# io-board-b-9.net
KiCad netlist of a schematic drawn in EAGLE
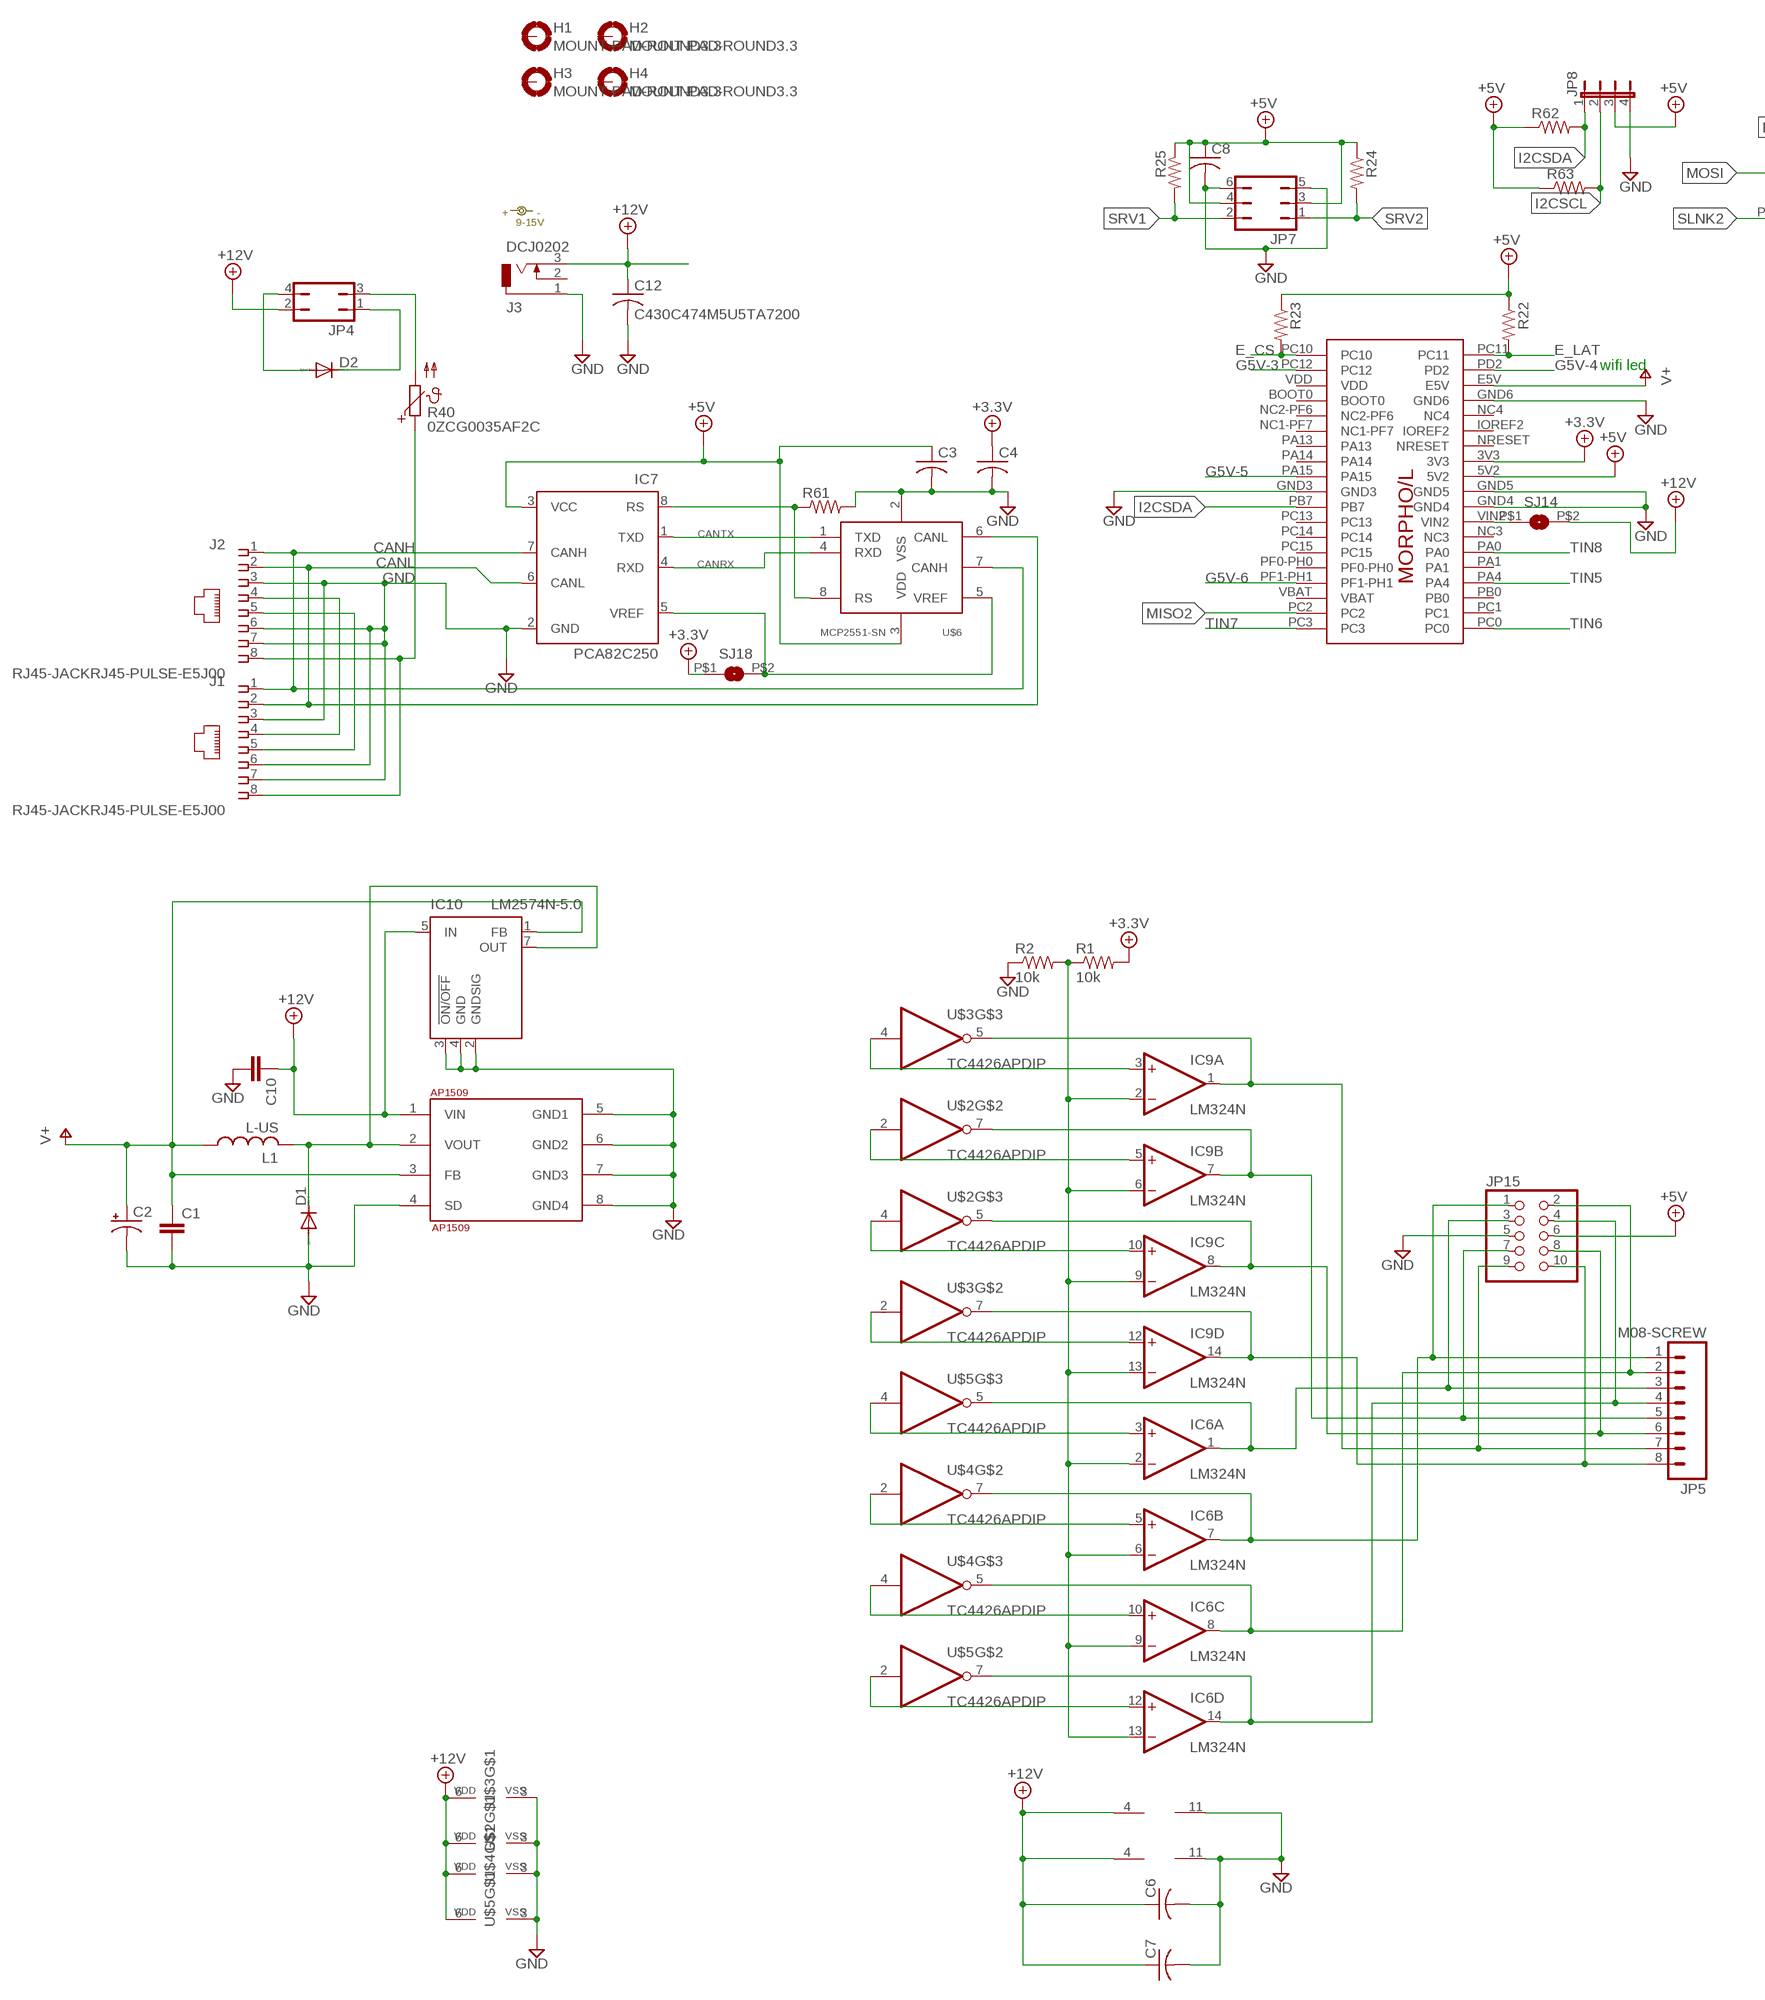
[diagram p0: schematic, sheet 1, part 1 of 2]
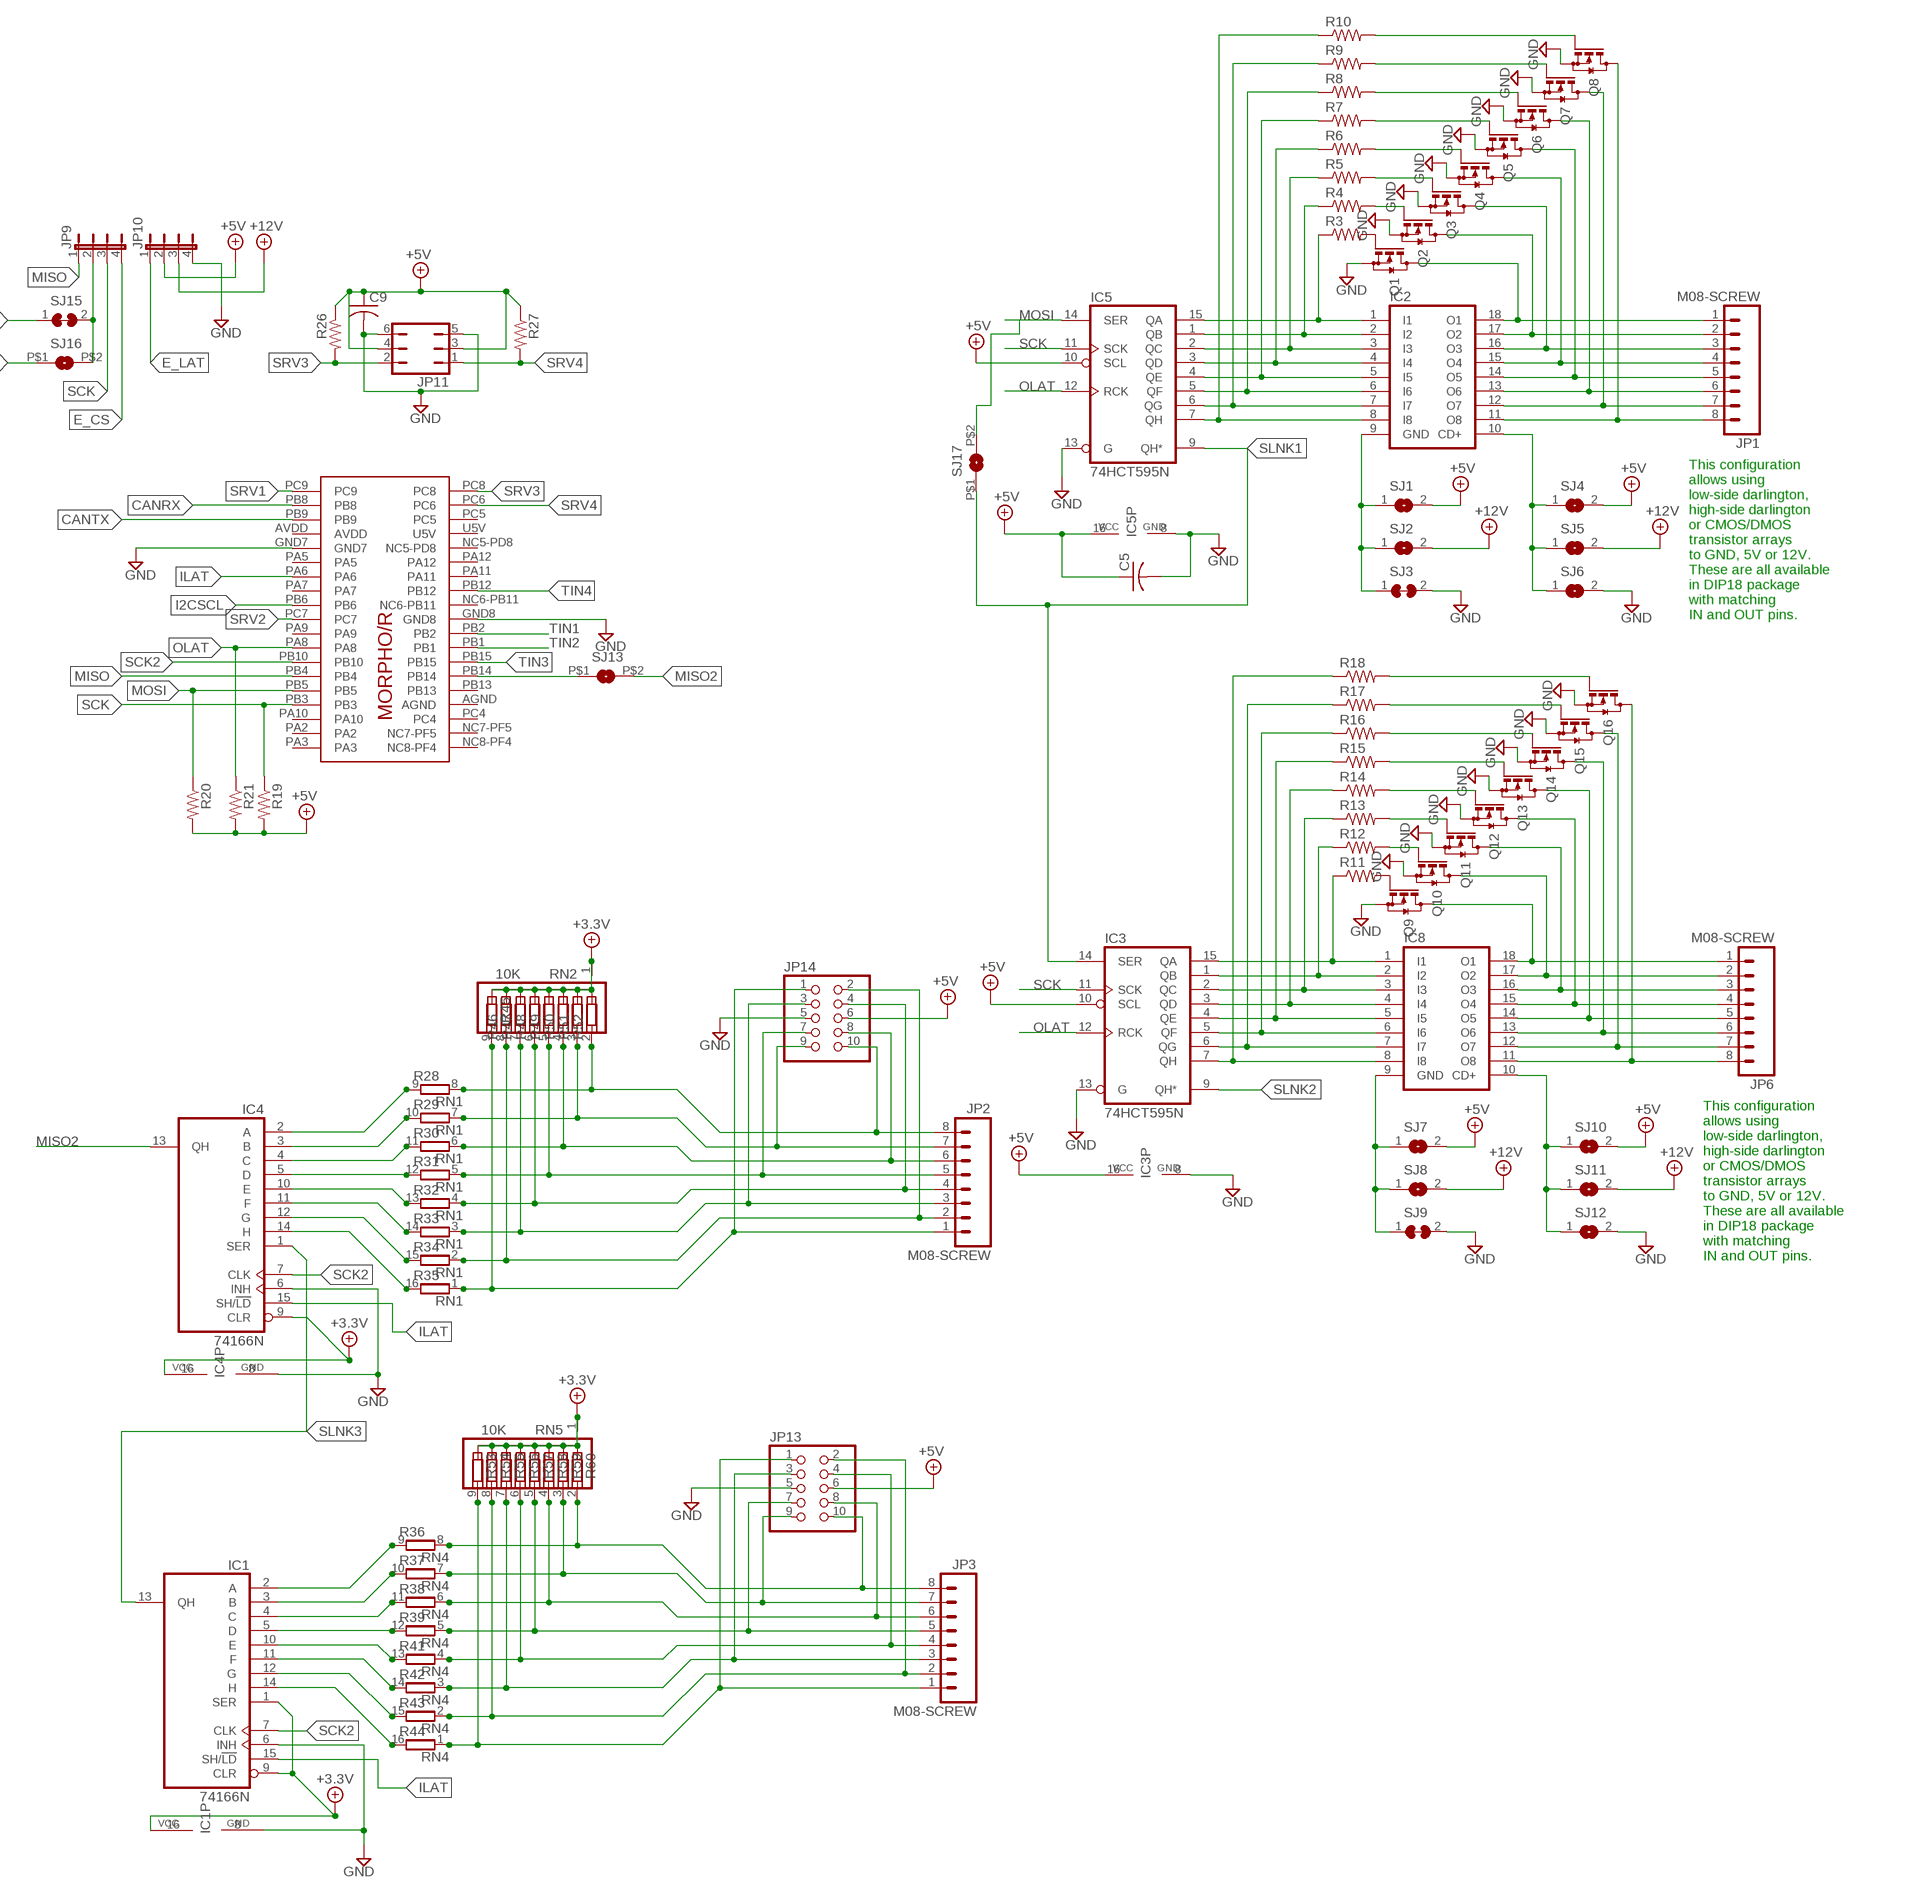
[diagram p1: schematic, sheet 1, part 2 of 2]

(export (version "E")
  (design (tool "Eeschema 10.0.6"))
  (components
    (comp (ref "+12V")
      (value "9-15V")
      (footprint "eagle-import:POWER_USAGE")
      (libsource (lib "eagle-import") (part "DOC-POWER_LABEL"))
    )
    (comp (ref "AP1509")
      (value "AP1509")
      (footprint "eagle-import:SO-08")
      (libsource (lib "eagle-import") (part "AP1509"))
    )
    (comp (ref "C1")
      (value "C-EUC1206")
      (footprint "eagle-import:C1206")
      (libsource (lib "eagle-import") (part "C-EUC1206"))
    )
    (comp (ref "C2")
      (value "CPOL-USE2.5-5")
      (footprint "eagle-import:E2,5-5")
      (libsource (lib "eagle-import") (part "CPOL-USE2.5-5"))
    )
    (comp (ref "C3")
      (value "C-USC0805")
      (footprint "eagle-import:C0805")
      (libsource (lib "eagle-import") (part "C-USC0805"))
    )
    (comp (ref "C4")
      (value "C-USC0805")
      (footprint "eagle-import:C0805")
      (libsource (lib "eagle-import") (part "C-USC0805"))
    )
    (comp (ref "C5")
      (value "C-USC0805")
      (footprint "eagle-import:C0805")
      (libsource (lib "eagle-import") (part "C-USC0805"))
    )
    (comp (ref "C6")
      (value "C-USC1206")
      (footprint "eagle-import:C1206")
      (libsource (lib "eagle-import") (part "C-USC1206"))
    )
    (comp (ref "C7")
      (value "C-USC1206")
      (footprint "eagle-import:C1206")
      (libsource (lib "eagle-import") (part "C-USC1206"))
    )
    (comp (ref "C8")
      (value "C-USC1206")
      (footprint "eagle-import:C1206")
      (libsource (lib "eagle-import") (part "C-USC1206"))
    )
    (comp (ref "C9")
      (value "C-USC1206")
      (footprint "eagle-import:C1206")
      (libsource (lib "eagle-import") (part "C-USC1206"))
    )
    (comp (ref "C10")
      (value "C-EUC1206")
      (footprint "eagle-import:C1206")
      (libsource (lib "eagle-import") (part "C-EUC1206"))
    )
    (comp (ref "C12")
      (value "C430C474M5U5TA7200")
      (footprint "eagle-import:C075-032X103")
      (libsource (lib "eagle-import") (part "C-US075-032X103"))
    )
    (comp (ref "D1")
      (value "DIODE-DO41-7.6")
      (footprint "eagle-import:DO41-7.6")
      (libsource (lib "eagle-import") (part "DIODE-DO41-7.6"))
    )
    (comp (ref "D2")
      (value "DIODE-DO41-7.6")
      (footprint "eagle-import:DO41-7.6")
      (libsource (lib "eagle-import") (part "DIODE-DO41-7.6"))
    )
    (comp (ref "H1")
      (value "MOUNT-PAD-ROUND3.3")
      (footprint "eagle-import:3,3-PAD")
      (libsource (lib "eagle-import") (part "MOUNT-PAD-ROUND3.3"))
    )
    (comp (ref "H2")
      (value "MOUNT-PAD-ROUND3.3")
      (footprint "eagle-import:3,3-PAD")
      (libsource (lib "eagle-import") (part "MOUNT-PAD-ROUND3.3"))
    )
    (comp (ref "H3")
      (value "MOUNT-PAD-ROUND3.3")
      (footprint "eagle-import:3,3-PAD")
      (libsource (lib "eagle-import") (part "MOUNT-PAD-ROUND3.3"))
    )
    (comp (ref "H4")
      (value "MOUNT-PAD-ROUND3.3")
      (footprint "eagle-import:3,3-PAD")
      (libsource (lib "eagle-import") (part "MOUNT-PAD-ROUND3.3"))
    )
    (comp (ref "IC1")
      (value "74166N")
      (footprint "eagle-import:DIL16")
      (libsource (lib "eagle-import") (part "74166N"))
    )
    (comp (ref "IC2")
      (value "ULN2803A")
      (footprint "eagle-import:DIL18-THIN")
      (libsource (lib "eagle-import") (part "ULN2803A"))
    )
    (comp (ref "IC3")
      (value "74HCT595N")
      (footprint "eagle-import:DIL16")
      (libsource (lib "eagle-import") (part "74595NHCT"))
    )
    (comp (ref "IC4")
      (value "74166N")
      (footprint "eagle-import:DIL16")
      (libsource (lib "eagle-import") (part "74166N"))
    )
    (comp (ref "IC5")
      (value "74HCT595N")
      (footprint "eagle-import:DIL16")
      (libsource (lib "eagle-import") (part "74595NHCT"))
    )
    (comp (ref "IC6")
      (value "LM324N")
      (footprint "eagle-import:DIL14")
      (libsource (lib "eagle-import") (part "LM324N"))
    )
    (comp (ref "IC7")
      (value "PCA82C250")
      (footprint "eagle-import:DIL08")
      (libsource (lib "eagle-import") (part "PCA82C250"))
    )
    (comp (ref "IC8")
      (value "ULN2803A")
      (footprint "eagle-import:DIL18-THIN")
      (libsource (lib "eagle-import") (part "ULN2803A"))
    )
    (comp (ref "IC9")
      (value "LM324N")
      (footprint "eagle-import:DIL14")
      (libsource (lib "eagle-import") (part "LM324N"))
    )
    (comp (ref "IC10")
      (value "LM2574N-5.0")
      (footprint "eagle-import:DIL08")
      (libsource (lib "eagle-import") (part "LM2574?-N5.0"))
    )
    (comp (ref "J1")
      (value "RJ45-JACKRJ45-PULSE-E5J00")
      (footprint "eagle-import:RJ45-PULSE-E5J88")
      (libsource (lib "eagle-import") (part "RJ45-JACKRJ45-PULSE-E5J00"))
    )
    (comp (ref "J2")
      (value "RJ45-JACKRJ45-PULSE-E5J00")
      (footprint "eagle-import:RJ45-PULSE-E5J88")
      (libsource (lib "eagle-import") (part "RJ45-JACKRJ45-PULSE-E5J00"))
    )
    (comp (ref "J3")
      (value "DCJ0202")
      (footprint "eagle-import:DCJ0202")
      (libsource (lib "eagle-import") (part "DCJ0202"))
    )
    (comp (ref "JP1")
      (value "M08-SCREW")
      (footprint "eagle-import:1X08_TERMINAL")
      (libsource (lib "eagle-import") (part "M08-SCREW"))
    )
    (comp (ref "JP2")
      (value "M08-SCREW")
      (footprint "eagle-import:1X08_TERMINAL")
      (libsource (lib "eagle-import") (part "M08-SCREW"))
    )
    (comp (ref "JP3")
      (value "M08-SCREW")
      (footprint "eagle-import:1X08_TERMINAL")
      (libsource (lib "eagle-import") (part "M08-SCREW"))
    )
    (comp (ref "JP4")
      (value "JP2Q")
      (footprint "eagle-import:JP2Q")
      (libsource (lib "eagle-import") (part "JP2Q"))
    )
    (comp (ref "JP5")
      (value "M08-SCREW")
      (footprint "eagle-import:1X08_TERMINAL")
      (libsource (lib "eagle-import") (part "M08-SCREW"))
    )
    (comp (ref "JP6")
      (value "M08-SCREW")
      (footprint "eagle-import:1X08_TERMINAL")
      (libsource (lib "eagle-import") (part "M08-SCREW"))
    )
    (comp (ref "JP7")
      (value "JP3Q")
      (footprint "eagle-import:JP3Q")
      (libsource (lib "eagle-import") (part "JP3Q"))
    )
    (comp (ref "JP8")
      (value "JP4-FLAT")
      (footprint "eagle-import:JP4F")
      (libsource (lib "eagle-import") (part "JP4-FLAT"))
    )
    (comp (ref "JP9")
      (value "JP4-FLAT")
      (footprint "eagle-import:JP4F")
      (libsource (lib "eagle-import") (part "JP4-FLAT"))
    )
    (comp (ref "JP10")
      (value "JP4-FLAT")
      (footprint "eagle-import:JP4F")
      (libsource (lib "eagle-import") (part "JP4-FLAT"))
    )
    (comp (ref "JP11")
      (value "JP3Q")
      (footprint "eagle-import:JP3Q")
      (libsource (lib "eagle-import") (part "JP3Q"))
    )
    (comp (ref "JP13")
      (value "PINHD-2X5CN")
      (footprint "eagle-import:CON10M")
      (libsource (lib "eagle-import") (part "PINHD-2X5CN"))
    )
    (comp (ref "JP14")
      (value "PINHD-2X5CN")
      (footprint "eagle-import:CON10M")
      (libsource (lib "eagle-import") (part "PINHD-2X5CN"))
    )
    (comp (ref "JP15")
      (value "PINHD-2X5CN")
      (footprint "eagle-import:CON10M")
      (libsource (lib "eagle-import") (part "PINHD-2X5CN"))
    )
    (comp (ref "L1")
      (value "L-US")
      (footprint "eagle-import:L5-8,5")
      (libsource (lib "eagle-import") (part "L-US"))
    )
    (comp (ref "Q1")
      (value "BSS123")
      (footprint "eagle-import:SOT23")
      (libsource (lib "eagle-import") (part "BSS123"))
    )
    (comp (ref "Q2")
      (value "BSS123")
      (footprint "eagle-import:SOT23")
      (libsource (lib "eagle-import") (part "BSS123"))
    )
    (comp (ref "Q3")
      (value "BSS123")
      (footprint "eagle-import:SOT23")
      (libsource (lib "eagle-import") (part "BSS123"))
    )
    (comp (ref "Q4")
      (value "BSS123")
      (footprint "eagle-import:SOT23")
      (libsource (lib "eagle-import") (part "BSS123"))
    )
    (comp (ref "Q5")
      (value "BSS123")
      (footprint "eagle-import:SOT23")
      (libsource (lib "eagle-import") (part "BSS123"))
    )
    (comp (ref "Q6")
      (value "BSS123")
      (footprint "eagle-import:SOT23")
      (libsource (lib "eagle-import") (part "BSS123"))
    )
    (comp (ref "Q7")
      (value "BSS123")
      (footprint "eagle-import:SOT23")
      (libsource (lib "eagle-import") (part "BSS123"))
    )
    (comp (ref "Q8")
      (value "BSS123")
      (footprint "eagle-import:SOT23")
      (libsource (lib "eagle-import") (part "BSS123"))
    )
    (comp (ref "Q9")
      (value "BSS123")
      (footprint "eagle-import:SOT23")
      (libsource (lib "eagle-import") (part "BSS123"))
    )
    (comp (ref "Q10")
      (value "BSS123")
      (footprint "eagle-import:SOT23")
      (libsource (lib "eagle-import") (part "BSS123"))
    )
    (comp (ref "Q11")
      (value "BSS123")
      (footprint "eagle-import:SOT23")
      (libsource (lib "eagle-import") (part "BSS123"))
    )
    (comp (ref "Q12")
      (value "BSS123")
      (footprint "eagle-import:SOT23")
      (libsource (lib "eagle-import") (part "BSS123"))
    )
    (comp (ref "Q13")
      (value "BSS123")
      (footprint "eagle-import:SOT23")
      (libsource (lib "eagle-import") (part "BSS123"))
    )
    (comp (ref "Q14")
      (value "BSS123")
      (footprint "eagle-import:SOT23")
      (libsource (lib "eagle-import") (part "BSS123"))
    )
    (comp (ref "Q15")
      (value "BSS123")
      (footprint "eagle-import:SOT23")
      (libsource (lib "eagle-import") (part "BSS123"))
    )
    (comp (ref "Q16")
      (value "BSS123")
      (footprint "eagle-import:SOT23")
      (libsource (lib "eagle-import") (part "BSS123"))
    )
    (comp (ref "R1")
      (value "10k")
      (footprint "eagle-import:R0805")
      (libsource (lib "eagle-import") (part "R-US_R0805"))
    )
    (comp (ref "R2")
      (value "10k")
      (footprint "eagle-import:R0805")
      (libsource (lib "eagle-import") (part "R-US_R0805"))
    )
    (comp (ref "R3")
      (value "R-US_R0603")
      (footprint "eagle-import:R0603")
      (libsource (lib "eagle-import") (part "R-US_R0603"))
    )
    (comp (ref "R4")
      (value "R-US_R0603")
      (footprint "eagle-import:R0603")
      (libsource (lib "eagle-import") (part "R-US_R0603"))
    )
    (comp (ref "R5")
      (value "R-US_R0603")
      (footprint "eagle-import:R0603")
      (libsource (lib "eagle-import") (part "R-US_R0603"))
    )
    (comp (ref "R6")
      (value "R-US_R0603")
      (footprint "eagle-import:R0603")
      (libsource (lib "eagle-import") (part "R-US_R0603"))
    )
    (comp (ref "R7")
      (value "R-US_R0603")
      (footprint "eagle-import:R0603")
      (libsource (lib "eagle-import") (part "R-US_R0603"))
    )
    (comp (ref "R8")
      (value "R-US_R0603")
      (footprint "eagle-import:R0603")
      (libsource (lib "eagle-import") (part "R-US_R0603"))
    )
    (comp (ref "R9")
      (value "R-US_R0603")
      (footprint "eagle-import:R0603")
      (libsource (lib "eagle-import") (part "R-US_R0603"))
    )
    (comp (ref "R10")
      (value "R-US_R0603")
      (footprint "eagle-import:R0603")
      (libsource (lib "eagle-import") (part "R-US_R0603"))
    )
    (comp (ref "R11")
      (value "R-US_R0603")
      (footprint "eagle-import:R0603")
      (libsource (lib "eagle-import") (part "R-US_R0603"))
    )
    (comp (ref "R12")
      (value "R-US_R0603")
      (footprint "eagle-import:R0603")
      (libsource (lib "eagle-import") (part "R-US_R0603"))
    )
    (comp (ref "R13")
      (value "R-US_R0603")
      (footprint "eagle-import:R0603")
      (libsource (lib "eagle-import") (part "R-US_R0603"))
    )
    (comp (ref "R14")
      (value "R-US_R0603")
      (footprint "eagle-import:R0603")
      (libsource (lib "eagle-import") (part "R-US_R0603"))
    )
    (comp (ref "R15")
      (value "R-US_R0603")
      (footprint "eagle-import:R0603")
      (libsource (lib "eagle-import") (part "R-US_R0603"))
    )
    (comp (ref "R16")
      (value "R-US_R0603")
      (footprint "eagle-import:R0603")
      (libsource (lib "eagle-import") (part "R-US_R0603"))
    )
    (comp (ref "R17")
      (value "R-US_R0603")
      (footprint "eagle-import:R0603")
      (libsource (lib "eagle-import") (part "R-US_R0603"))
    )
    (comp (ref "R18")
      (value "R-US_R0603")
      (footprint "eagle-import:R0603")
      (libsource (lib "eagle-import") (part "R-US_R0603"))
    )
    (comp (ref "R19")
      (value "R-US_R0805")
      (footprint "eagle-import:R0805")
      (libsource (lib "eagle-import") (part "rcl_334_R-US_R0805"))
    )
    (comp (ref "R20")
      (value "R-US_R0805")
      (footprint "eagle-import:R0805")
      (libsource (lib "eagle-import") (part "rcl_334_R-US_R0805"))
    )
    (comp (ref "R21")
      (value "R-US_R0805")
      (footprint "eagle-import:R0805")
      (libsource (lib "eagle-import") (part "rcl_334_R-US_R0805"))
    )
    (comp (ref "R22")
      (value "R-US_R0805")
      (footprint "eagle-import:R0805")
      (libsource (lib "eagle-import") (part "rcl_334_R-US_R0805"))
    )
    (comp (ref "R23")
      (value "R-US_R0805")
      (footprint "eagle-import:R0805")
      (libsource (lib "eagle-import") (part "rcl_334_R-US_R0805"))
    )
    (comp (ref "R24")
      (value "R-US_R0805")
      (footprint "eagle-import:R0805")
      (libsource (lib "eagle-import") (part "rcl_334_R-US_R0805"))
    )
    (comp (ref "R25")
      (value "R-US_R0805")
      (footprint "eagle-import:R0805")
      (libsource (lib "eagle-import") (part "rcl_334_R-US_R0805"))
    )
    (comp (ref "R26")
      (value "R-US_R0805")
      (footprint "eagle-import:R0805")
      (libsource (lib "eagle-import") (part "rcl_334_R-US_R0805"))
    )
    (comp (ref "R27")
      (value "R-US_R0805")
      (footprint "eagle-import:R0805")
      (libsource (lib "eagle-import") (part "rcl_334_R-US_R0805"))
    )
    (comp (ref "R28")
      (value "R-EU_R0603")
      (footprint "eagle-import:R0603")
      (libsource (lib "eagle-import") (part "R-EU_R0603"))
    )
    (comp (ref "R29")
      (value "R-EU_R0603")
      (footprint "eagle-import:R0603")
      (libsource (lib "eagle-import") (part "R-EU_R0603"))
    )
    (comp (ref "R30")
      (value "R-EU_R0603")
      (footprint "eagle-import:R0603")
      (libsource (lib "eagle-import") (part "R-EU_R0603"))
    )
    (comp (ref "R31")
      (value "R-EU_R0603")
      (footprint "eagle-import:R0603")
      (libsource (lib "eagle-import") (part "R-EU_R0603"))
    )
    (comp (ref "R32")
      (value "R-EU_R0603")
      (footprint "eagle-import:R0603")
      (libsource (lib "eagle-import") (part "R-EU_R0603"))
    )
    (comp (ref "R33")
      (value "R-EU_R0603")
      (footprint "eagle-import:R0603")
      (libsource (lib "eagle-import") (part "R-EU_R0603"))
    )
    (comp (ref "R34")
      (value "R-EU_R0603")
      (footprint "eagle-import:R0603")
      (libsource (lib "eagle-import") (part "R-EU_R0603"))
    )
    (comp (ref "R35")
      (value "R-EU_R0603")
      (footprint "eagle-import:R0603")
      (libsource (lib "eagle-import") (part "R-EU_R0603"))
    )
    (comp (ref "R36")
      (value "R-EU_R0603")
      (footprint "eagle-import:R0603")
      (libsource (lib "eagle-import") (part "R-EU_R0603"))
    )
    (comp (ref "R37")
      (value "R-EU_R0603")
      (footprint "eagle-import:R0603")
      (libsource (lib "eagle-import") (part "R-EU_R0603"))
    )
    (comp (ref "R38")
      (value "R-EU_R0603")
      (footprint "eagle-import:R0603")
      (libsource (lib "eagle-import") (part "R-EU_R0603"))
    )
    (comp (ref "R39")
      (value "R-EU_R0603")
      (footprint "eagle-import:R0603")
      (libsource (lib "eagle-import") (part "R-EU_R0603"))
    )
    (comp (ref "R40")
      (value "0ZCG0035AF2C")
      (footprint "eagle-import:PTC1812")
      (libsource (lib "eagle-import") (part "PTC_1812"))
    )
    (comp (ref "R41")
      (value "R-EU_R0603")
      (footprint "eagle-import:R0603")
      (libsource (lib "eagle-import") (part "R-EU_R0603"))
    )
    (comp (ref "R42")
      (value "R-EU_R0603")
      (footprint "eagle-import:R0603")
      (libsource (lib "eagle-import") (part "R-EU_R0603"))
    )
    (comp (ref "R43")
      (value "R-EU_R0603")
      (footprint "eagle-import:R0603")
      (libsource (lib "eagle-import") (part "R-EU_R0603"))
    )
    (comp (ref "R44")
      (value "R-EU_R0603")
      (footprint "eagle-import:R0603")
      (libsource (lib "eagle-import") (part "R-EU_R0603"))
    )
    (comp (ref "R45")
      (value "R-EU_R0603")
      (footprint "eagle-import:R0603")
      (libsource (lib "eagle-import") (part "R-EU_R0603"))
    )
    (comp (ref "R46")
      (value "R-EU_R0603")
      (footprint "eagle-import:R0603")
      (libsource (lib "eagle-import") (part "R-EU_R0603"))
    )
    (comp (ref "R47")
      (value "R-EU_R0603")
      (footprint "eagle-import:R0603")
      (libsource (lib "eagle-import") (part "R-EU_R0603"))
    )
    (comp (ref "R48")
      (value "R-EU_R0603")
      (footprint "eagle-import:R0603")
      (libsource (lib "eagle-import") (part "R-EU_R0603"))
    )
    (comp (ref "R49")
      (value "R-EU_R0603")
      (footprint "eagle-import:R0603")
      (libsource (lib "eagle-import") (part "R-EU_R0603"))
    )
    (comp (ref "R50")
      (value "R-EU_R0603")
      (footprint "eagle-import:R0603")
      (libsource (lib "eagle-import") (part "R-EU_R0603"))
    )
    (comp (ref "R51")
      (value "R-EU_R0603")
      (footprint "eagle-import:R0603")
      (libsource (lib "eagle-import") (part "R-EU_R0603"))
    )
    (comp (ref "R52")
      (value "R-EU_R0603")
      (footprint "eagle-import:R0603")
      (libsource (lib "eagle-import") (part "R-EU_R0603"))
    )
    (comp (ref "R53")
      (value "R-EU_R0603")
      (footprint "eagle-import:R0603")
      (libsource (lib "eagle-import") (part "R-EU_R0603"))
    )
    (comp (ref "R54")
      (value "R-EU_R0603")
      (footprint "eagle-import:R0603")
      (libsource (lib "eagle-import") (part "R-EU_R0603"))
    )
    (comp (ref "R55")
      (value "R-EU_R0603")
      (footprint "eagle-import:R0603")
      (libsource (lib "eagle-import") (part "R-EU_R0603"))
    )
    (comp (ref "R56")
      (value "R-EU_R0603")
      (footprint "eagle-import:R0603")
      (libsource (lib "eagle-import") (part "R-EU_R0603"))
    )
    (comp (ref "R57")
      (value "R-EU_R0603")
      (footprint "eagle-import:R0603")
      (libsource (lib "eagle-import") (part "R-EU_R0603"))
    )
    (comp (ref "R58")
      (value "R-EU_R0603")
      (footprint "eagle-import:R0603")
      (libsource (lib "eagle-import") (part "R-EU_R0603"))
    )
    (comp (ref "R59")
      (value "R-EU_R0603")
      (footprint "eagle-import:R0603")
      (libsource (lib "eagle-import") (part "R-EU_R0603"))
    )
    (comp (ref "R60")
      (value "R-EU_R0603")
      (footprint "eagle-import:R0603")
      (libsource (lib "eagle-import") (part "R-EU_R0603"))
    )
    (comp (ref "R61")
      (value "R-US_R0805")
      (footprint "eagle-import:R0805")
      (libsource (lib "eagle-import") (part "rcl_334_R-US_R0805"))
    )
    (comp (ref "R62")
      (value "R-US_R0805")
      (footprint "eagle-import:R0805")
      (libsource (lib "eagle-import") (part "rcl_334_R-US_R0805"))
    )
    (comp (ref "R63")
      (value "R-US_R0805")
      (footprint "eagle-import:R0805")
      (libsource (lib "eagle-import") (part "rcl_334_R-US_R0805"))
    )
    (comp (ref "RN1")
      (value "8R-P")
      (footprint "eagle-import:DIL16")
      (libsource (lib "eagle-import") (part "8R-P"))
    )
    (comp (ref "RN2")
      (value "10K")
      (footprint "eagle-import:SIL9")
      (libsource (lib "eagle-import") (part "G08R"))
    )
    (comp (ref "RN4")
      (value "8R-P")
      (footprint "eagle-import:DIL16")
      (libsource (lib "eagle-import") (part "8R-P"))
    )
    (comp (ref "RN5")
      (value "10K")
      (footprint "eagle-import:SIL9")
      (libsource (lib "eagle-import") (part "G08R"))
    )
    (comp (ref "SJ1")
      (value "SJ")
      (footprint "eagle-import:SJ-RND")
      (libsource (lib "eagle-import") (part "SJ"))
    )
    (comp (ref "SJ2")
      (value "SJ")
      (footprint "eagle-import:SJ-RND")
      (libsource (lib "eagle-import") (part "SJ"))
    )
    (comp (ref "SJ3")
      (value "SJ-C")
      (footprint "eagle-import:SJW-C")
      (libsource (lib "eagle-import") (part "SJ-C"))
    )
    (comp (ref "SJ4")
      (value "SJ")
      (footprint "eagle-import:SJ-RND")
      (libsource (lib "eagle-import") (part "SJ"))
    )
    (comp (ref "SJ5")
      (value "SJ")
      (footprint "eagle-import:SJ-RND")
      (libsource (lib "eagle-import") (part "SJ"))
    )
    (comp (ref "SJ6")
      (value "SJ")
      (footprint "eagle-import:SJ-RND")
      (libsource (lib "eagle-import") (part "SJ"))
    )
    (comp (ref "SJ7")
      (value "SJ")
      (footprint "eagle-import:SJ-RND")
      (libsource (lib "eagle-import") (part "SJ"))
    )
    (comp (ref "SJ8")
      (value "SJ")
      (footprint "eagle-import:SJ-RND")
      (libsource (lib "eagle-import") (part "SJ"))
    )
    (comp (ref "SJ9")
      (value "SJ-C")
      (footprint "eagle-import:SJW-C")
      (libsource (lib "eagle-import") (part "SJ-C"))
    )
    (comp (ref "SJ10")
      (value "SJ")
      (footprint "eagle-import:SJ-RND")
      (libsource (lib "eagle-import") (part "SJ"))
    )
    (comp (ref "SJ11")
      (value "SJ")
      (footprint "eagle-import:SJ-RND")
      (libsource (lib "eagle-import") (part "SJ"))
    )
    (comp (ref "SJ12")
      (value "SJ")
      (footprint "eagle-import:SJ-RND")
      (libsource (lib "eagle-import") (part "SJ"))
    )
    (comp (ref "SJ13")
      (value "SJRND2")
      (footprint "eagle-import:SJ_RND2")
      (libsource (lib "eagle-import") (part "SJRND2"))
    )
    (comp (ref "SJ14")
      (value "SJRND2")
      (footprint "eagle-import:SJ_RND2")
      (libsource (lib "eagle-import") (part "SJRND2"))
    )
    (comp (ref "SJ15")
      (value "SJ-C")
      (footprint "eagle-import:SJW-C")
      (libsource (lib "eagle-import") (part "SJ-C"))
    )
    (comp (ref "SJ16")
      (value "SJRND2")
      (footprint "eagle-import:SJ_RND2")
      (libsource (lib "eagle-import") (part "SJRND2"))
    )
    (comp (ref "SJ17")
      (value "SJRND2")
      (footprint "eagle-import:SJ_RND2")
      (libsource (lib "eagle-import") (part "SJRND2"))
    )
    (comp (ref "SJ18")
      (value "SJRND2")
      (footprint "eagle-import:SJ_RND2")
      (libsource (lib "eagle-import") (part "SJRND2"))
    )
    (comp (ref "U$1")
      (value "NUCLEO_64_GENERIC")
      (footprint "eagle-import:NUCLEO_BRD_BASE64")
      (libsource (lib "eagle-import") (part "NUCLEO_64_GENERIC"))
    )
    (comp (ref "U$2")
      (value "TC4426APDIP")
      (footprint "eagle-import:DIL08-LONG")
      (libsource (lib "eagle-import") (part "TC4426APDIP"))
    )
    (comp (ref "U$3")
      (value "TC4426APDIP")
      (footprint "eagle-import:DIL08-LONG")
      (libsource (lib "eagle-import") (part "TC4426APDIP"))
    )
    (comp (ref "U$4")
      (value "TC4426APDIP")
      (footprint "eagle-import:DIL08-LONG")
      (libsource (lib "eagle-import") (part "TC4426APDIP"))
    )
    (comp (ref "U$5")
      (value "TC4426APDIP")
      (footprint "eagle-import:DIL08-LONG")
      (libsource (lib "eagle-import") (part "TC4426APDIP"))
    )
    (comp (ref "U$6")
      (value "MCP2551-SN")
      (footprint "eagle-import:SO-08")
      (libsource (lib "eagle-import") (part "MCP2551-SN"))
    )
  )
  (nets
    (net (code "1") (name "+3.3V") (class "Default")
      (node (ref "C4") (pin "1") (pinfunction "1_1") (pintype "passive"))
      (node (ref "IC1") (pin "1") (pinfunction "SER_1") (pintype "input"))
      (node (ref "IC1") (pin "16") (pinfunction "VCC_16") (pintype "power_in"))
      (node (ref "IC1") (pin "9") (pinfunction "CLR_9") (pintype "input"))
      (node (ref "IC4") (pin "16") (pinfunction "VCC_16") (pintype "power_in"))
      (node (ref "IC4") (pin "9") (pinfunction "CLR_9") (pintype "input"))
      (node (ref "R1") (pin "2") (pinfunction "2_2") (pintype "passive"))
      (node (ref "R45") (pin "1") (pinfunction "1_1") (pintype "passive"))
      (node (ref "R46") (pin "2") (pinfunction "2_2") (pintype "passive"))
      (node (ref "R47") (pin "2") (pinfunction "2_2") (pintype "passive"))
      (node (ref "R48") (pin "2") (pinfunction "2_2") (pintype "passive"))
      (node (ref "R49") (pin "2") (pinfunction "2_2") (pintype "passive"))
      (node (ref "R50") (pin "2") (pinfunction "2_2") (pintype "passive"))
      (node (ref "R51") (pin "2") (pinfunction "2_2") (pintype "passive"))
      (node (ref "R52") (pin "2") (pinfunction "2_2") (pintype "passive"))
      (node (ref "R53") (pin "1") (pinfunction "1_1") (pintype "passive"))
      (node (ref "R54") (pin "1") (pinfunction "1_1") (pintype "passive"))
      (node (ref "R55") (pin "1") (pinfunction "1_1") (pintype "passive"))
      (node (ref "R56") (pin "1") (pinfunction "1_1") (pintype "passive"))
      (node (ref "R57") (pin "1") (pinfunction "1_1") (pintype "passive"))
      (node (ref "R58") (pin "1") (pinfunction "1_1") (pintype "passive"))
      (node (ref "R59") (pin "1") (pinfunction "1_1") (pintype "passive"))
      (node (ref "R60") (pin "1") (pinfunction "1_1") (pintype "passive"))
      (node (ref "RN2") (pin "1") (pinfunction "1_1") (pintype "passive"))
      (node (ref "RN5") (pin "1") (pinfunction "1_1") (pintype "passive"))
      (node (ref "SJ18") (pin "P$1") (pinfunction "1_P$1") (pintype "passive"))
      (node (ref "U$1") (pin "3V3") (pinfunction "3V3_3V3") (pintype "power_in"))
    )
    (net (code "2") (name "+5V") (class "Default")
      (node (ref "C3") (pin "1") (pinfunction "1_1") (pintype "passive"))
      (node (ref "C5") (pin "1") (pinfunction "1_1") (pintype "passive"))
      (node (ref "C8") (pin "1") (pinfunction "1_1") (pintype "passive"))
      (node (ref "C9") (pin "1") (pinfunction "1_1") (pintype "passive"))
      (node (ref "IC3") (pin "10") (pinfunction "SCL_10") (pintype "input"))
      (node (ref "IC3") (pin "16") (pinfunction "VCC_16") (pintype "power_in"))
      (node (ref "IC5") (pin "10") (pinfunction "SCL_10") (pintype "input"))
      (node (ref "IC5") (pin "16") (pinfunction "VCC_16") (pintype "power_in"))
      (node (ref "IC7") (pin "3") (pinfunction "VCC_3") (pintype "power_in"))
      (node (ref "JP10") (pin "2") (pinfunction "2_2") (pintype "passive"))
      (node (ref "JP11") (pin "3") (pinfunction "3_3") (pintype "passive"))
      (node (ref "JP11") (pin "4") (pinfunction "4_4") (pintype "passive"))
      (node (ref "JP13") (pin "6") (pinfunction "6_6") (pintype "passive"))
      (node (ref "JP14") (pin "6") (pinfunction "6_6") (pintype "passive"))
      (node (ref "JP15") (pin "6") (pinfunction "6_6") (pintype "passive"))
      (node (ref "JP7") (pin "3") (pinfunction "3_3") (pintype "passive"))
      (node (ref "JP7") (pin "4") (pinfunction "4_4") (pintype "passive"))
      (node (ref "JP8") (pin "3") (pinfunction "3_3") (pintype "passive"))
      (node (ref "R19") (pin "2") (pinfunction "2_2") (pintype "passive"))
      (node (ref "R20") (pin "2") (pinfunction "2_2") (pintype "passive"))
      (node (ref "R21") (pin "2") (pinfunction "2_2") (pintype "passive"))
      (node (ref "R22") (pin "1") (pinfunction "1_1") (pintype "passive"))
      (node (ref "R23") (pin "1") (pinfunction "1_1") (pintype "passive"))
      (node (ref "R24") (pin "1") (pinfunction "1_1") (pintype "passive"))
      (node (ref "R25") (pin "1") (pinfunction "1_1") (pintype "passive"))
      (node (ref "R26") (pin "1") (pinfunction "1_1") (pintype "passive"))
      (node (ref "R27") (pin "1") (pinfunction "1_1") (pintype "passive"))
      (node (ref "R62") (pin "1") (pinfunction "1_1") (pintype "passive"))
      (node (ref "R63") (pin "1") (pinfunction "1_1") (pintype "passive"))
      (node (ref "SJ1") (pin "2") (pinfunction "2_2") (pintype "passive"))
      (node (ref "SJ10") (pin "2") (pinfunction "2_2") (pintype "passive"))
      (node (ref "SJ4") (pin "2") (pinfunction "2_2") (pintype "passive"))
      (node (ref "SJ7") (pin "2") (pinfunction "2_2") (pintype "passive"))
      (node (ref "U$1") (pin "5V2") (pinfunction "5V2_5V2") (pintype "power_in"))
      (node (ref "U$6") (pin "3") (pinfunction "VDD_3") (pintype "power_in"))
    )
    (net (code "3") (name "+12V") (class "Default")
      (node (ref "AP1509") (pin "1") (pinfunction "VIN_1") (pintype "bidirectional"))
      (node (ref "C10") (pin "1") (pinfunction "1_1") (pintype "passive"))
      (node (ref "C12") (pin "1") (pinfunction "1_1") (pintype "passive"))
      (node (ref "C6") (pin "1") (pinfunction "1_1") (pintype "passive"))
      (node (ref "C7") (pin "1") (pinfunction "1_1") (pintype "passive"))
      (node (ref "IC10") (pin "5") (pinfunction "IN_5") (pintype "input"))
      (node (ref "IC6") (pin "4") (pinfunction "V+_4") (pintype "power_in"))
      (node (ref "IC9") (pin "4") (pinfunction "V+_4") (pintype "power_in"))
      (node (ref "J3") (pin "3") (pinfunction "3_3") (pintype "passive"))
      (node (ref "JP10") (pin "3") (pinfunction "3_3") (pintype "passive"))
      (node (ref "JP4") (pin "2") (pinfunction "2_2") (pintype "passive"))
      (node (ref "SJ11") (pin "2") (pinfunction "2_2") (pintype "passive"))
      (node (ref "SJ14") (pin "P$2") (pinfunction "2_P$2") (pintype "passive"))
      (node (ref "SJ2") (pin "2") (pinfunction "2_2") (pintype "passive"))
      (node (ref "SJ5") (pin "2") (pinfunction "2_2") (pintype "passive"))
      (node (ref "SJ8") (pin "2") (pinfunction "2_2") (pintype "passive"))
      (node (ref "U$2") (pin "6") (pinfunction "VDD_6") (pintype "power_in"))
      (node (ref "U$3") (pin "6") (pinfunction "VDD_6") (pintype "power_in"))
      (node (ref "U$4") (pin "6") (pinfunction "VDD_6") (pintype "power_in"))
      (node (ref "U$5") (pin "6") (pinfunction "VDD_6") (pintype "power_in"))
    )
    (net (code "4") (name "/AGND") (class "Default")
      (node (ref "U$1") (pin "AGND") (pinfunction "AGND_AGND") (pintype "power_in"))
    )
    (net (code "5") (name "/AVDD") (class "Default")
      (node (ref "U$1") (pin "AVDD") (pinfunction "AVDD_AVDD") (pintype "power_in"))
    )
    (net (code "6") (name "/CANH") (class "Default")
      (node (ref "IC7") (pin "7") (pinfunction "CANH_7") (pintype "bidirectional"))
      (node (ref "J1") (pin "1") (pinfunction "1_1") (pintype "passive"))
      (node (ref "J2") (pin "1") (pinfunction "1_1") (pintype "passive"))
      (node (ref "U$6") (pin "7") (pinfunction "CANH_7") (pintype "bidirectional"))
    )
    (net (code "7") (name "/CANL") (class "Default")
      (node (ref "IC7") (pin "6") (pinfunction "CANL_6") (pintype "bidirectional"))
      (node (ref "J1") (pin "2") (pinfunction "2_2") (pintype "passive"))
      (node (ref "J2") (pin "2") (pinfunction "2_2") (pintype "passive"))
      (node (ref "U$6") (pin "6") (pinfunction "CANL_6") (pintype "bidirectional"))
    )
    (net (code "8") (name "/G5V-3") (class "Default")
      (node (ref "U$1") (pin "PC12") (pinfunction "PC12_PC12") (pintype "bidirectional"))
    )
    (net (code "9") (name "/G5V-4") (class "Default")
      (node (ref "U$1") (pin "PD2") (pinfunction "PD2_PD2") (pintype "bidirectional"))
    )
    (net (code "10") (name "/G5V-5") (class "Default")
      (node (ref "U$1") (pin "PA15") (pinfunction "PA15_PA15") (pintype "bidirectional"))
    )
    (net (code "11") (name "/G5V-6") (class "Default")
      (node (ref "U$1") (pin "PF1-PH1") (pinfunction "PF1-PH1_PF1-PH1") (pintype "bidirectional"))
    )
    (net (code "12") (name "/TIN1") (class "Default")
      (node (ref "IC9") (pin "3") (pinfunction "+IN_3") (pintype "input"))
      (node (ref "U$1") (pin "PB2") (pinfunction "PB2_PB2") (pintype "bidirectional"))
      (node (ref "U$3") (pin "4") (pinfunction "I_4") (pintype "input"))
    )
    (net (code "13") (name "/TIN2") (class "Default")
      (node (ref "IC9") (pin "5") (pinfunction "+IN_5") (pintype "input"))
      (node (ref "U$1") (pin "PB1") (pinfunction "PB1_PB1") (pintype "bidirectional"))
      (node (ref "U$2") (pin "2") (pinfunction "I_2") (pintype "input"))
    )
    (net (code "14") (name "/TIN5") (class "Default")
      (node (ref "IC6") (pin "3") (pinfunction "+IN_3") (pintype "input"))
      (node (ref "U$1") (pin "PA4") (pinfunction "PA4_PA4") (pintype "bidirectional"))
      (node (ref "U$5") (pin "4") (pinfunction "I_4") (pintype "input"))
    )
    (net (code "15") (name "/TIN6") (class "Default")
      (node (ref "IC6") (pin "5") (pinfunction "+IN_5") (pintype "input"))
      (node (ref "U$1") (pin "PC0") (pinfunction "PC0_PC0") (pintype "bidirectional"))
      (node (ref "U$4") (pin "2") (pinfunction "I_2") (pintype "input"))
    )
    (net (code "16") (name "/TIN7") (class "Default")
      (node (ref "IC6") (pin "10") (pinfunction "+IN_10") (pintype "input"))
      (node (ref "U$1") (pin "PC3") (pinfunction "PC3_PC3") (pintype "bidirectional"))
      (node (ref "U$4") (pin "4") (pinfunction "I_4") (pintype "input"))
    )
    (net (code "17") (name "/TIN8") (class "Default")
      (node (ref "IC6") (pin "12") (pinfunction "+IN_12") (pintype "input"))
      (node (ref "U$1") (pin "PA0") (pinfunction "PA0_PA0") (pintype "bidirectional"))
      (node (ref "U$5") (pin "2") (pinfunction "I_2") (pintype "input"))
    )
    (net (code "18") (name "/U5V") (class "Default")
      (node (ref "U$1") (pin "U5V") (pinfunction "U5V_U5V") (pintype "power_in"))
    )
    (net (code "19") (name "/VBAT") (class "Default")
      (node (ref "U$1") (pin "VBAT") (pinfunction "VBAT_VBAT") (pintype "power_in"))
    )
    (net (code "20") (name "/VDD") (class "Default")
      (node (ref "U$1") (pin "VDD") (pinfunction "VDD_VDD") (pintype "power_in"))
    )
    (net (code "21") (name "CANRX") (class "Default")
      (node (ref "IC7") (pin "4") (pinfunction "RXD_4") (pintype "output"))
      (node (ref "U$1") (pin "PB8") (pinfunction "PB8_PB8") (pintype "bidirectional"))
      (node (ref "U$6") (pin "4") (pinfunction "RXD_4") (pintype "bidirectional"))
    )
    (net (code "22") (name "CANTX") (class "Default")
      (node (ref "IC7") (pin "1") (pinfunction "TXD_1") (pintype "input"))
      (node (ref "U$1") (pin "PB9") (pinfunction "PB9_PB9") (pintype "bidirectional"))
      (node (ref "U$6") (pin "1") (pinfunction "TXD_1") (pintype "bidirectional"))
    )
    (net (code "23") (name "E_CS") (class "Default")
      (node (ref "JP9") (pin "4") (pinfunction "4_4") (pintype "passive"))
      (node (ref "R23") (pin "2") (pinfunction "2_2") (pintype "passive"))
      (node (ref "U$1") (pin "PC10") (pinfunction "PC10_PC10") (pintype "bidirectional"))
    )
    (net (code "24") (name "E_LAT") (class "Default")
      (node (ref "JP10") (pin "1") (pinfunction "1_1") (pintype "passive"))
      (node (ref "R22") (pin "2") (pinfunction "2_2") (pintype "passive"))
      (node (ref "U$1") (pin "PC11") (pinfunction "PC11_PC11") (pintype "bidirectional"))
    )
    (net (code "25") (name "GND") (class "Default")
      (node (ref "AP1509") (pin "4") (pinfunction "SD_4") (pintype "bidirectional"))
      (node (ref "AP1509") (pin "5") (pinfunction "GND1_5") (pintype "power_in"))
      (node (ref "AP1509") (pin "6") (pinfunction "GND2_6") (pintype "power_in"))
      (node (ref "AP1509") (pin "7") (pinfunction "GND3_7") (pintype "power_in"))
      (node (ref "AP1509") (pin "8") (pinfunction "GND4_8") (pintype "power_in"))
      (node (ref "C1") (pin "2") (pinfunction "2_2") (pintype "passive"))
      (node (ref "C10") (pin "2") (pinfunction "2_2") (pintype "passive"))
      (node (ref "C12") (pin "2") (pinfunction "2_2") (pintype "passive"))
      (node (ref "C2") (pin "-") (pinfunction "-_-") (pintype "passive"))
      (node (ref "C3") (pin "2") (pinfunction "2_2") (pintype "passive"))
      (node (ref "C4") (pin "2") (pinfunction "2_2") (pintype "passive"))
      (node (ref "C5") (pin "2") (pinfunction "2_2") (pintype "passive"))
      (node (ref "C6") (pin "2") (pinfunction "2_2") (pintype "passive"))
      (node (ref "C7") (pin "2") (pinfunction "2_2") (pintype "passive"))
      (node (ref "C8") (pin "2") (pinfunction "2_2") (pintype "passive"))
      (node (ref "C9") (pin "2") (pinfunction "2_2") (pintype "passive"))
      (node (ref "D1") (pin "A") (pinfunction "A_A") (pintype "passive"))
      (node (ref "IC1") (pin "6") (pinfunction "INH_6") (pintype "input"))
      (node (ref "IC1") (pin "8") (pinfunction "GND_8") (pintype "power_in"))
      (node (ref "IC10") (pin "2") (pinfunction "GNDSIG_2") (pintype "input"))
      (node (ref "IC10") (pin "3") (pinfunction "~{ON/OFF}_3") (pintype "input"))
      (node (ref "IC10") (pin "4") (pinfunction "GND_4") (pintype "power_in"))
      (node (ref "IC3") (pin "13") (pinfunction "G_13") (pintype "input"))
      (node (ref "IC3") (pin "8") (pinfunction "GND_8") (pintype "power_in"))
      (node (ref "IC4") (pin "6") (pinfunction "INH_6") (pintype "input"))
      (node (ref "IC4") (pin "8") (pinfunction "GND_8") (pintype "power_in"))
      (node (ref "IC5") (pin "13") (pinfunction "G_13") (pintype "input"))
      (node (ref "IC5") (pin "8") (pinfunction "GND_8") (pintype "power_in"))
      (node (ref "IC6") (pin "11") (pinfunction "V-_11") (pintype "power_in"))
      (node (ref "IC7") (pin "2") (pinfunction "GND_2") (pintype "power_in"))
      (node (ref "IC9") (pin "11") (pinfunction "V-_11") (pintype "power_in"))
      (node (ref "J1") (pin "3") (pinfunction "3_3") (pintype "passive"))
      (node (ref "J1") (pin "6") (pinfunction "6_6") (pintype "passive"))
      (node (ref "J1") (pin "7") (pinfunction "7_7") (pintype "passive"))
      (node (ref "J2") (pin "3") (pinfunction "3_3") (pintype "passive"))
      (node (ref "J2") (pin "6") (pinfunction "6_6") (pintype "passive"))
      (node (ref "J2") (pin "7") (pinfunction "7_7") (pintype "passive"))
      (node (ref "J3") (pin "1") (pinfunction "1_1") (pintype "passive"))
      (node (ref "JP10") (pin "4") (pinfunction "4_4") (pintype "passive"))
      (node (ref "JP11") (pin "5") (pinfunction "5_5") (pintype "passive"))
      (node (ref "JP11") (pin "6") (pinfunction "6_6") (pintype "passive"))
      (node (ref "JP13") (pin "5") (pinfunction "5_5") (pintype "passive"))
      (node (ref "JP14") (pin "5") (pinfunction "5_5") (pintype "passive"))
      (node (ref "JP15") (pin "5") (pinfunction "5_5") (pintype "passive"))
      (node (ref "JP7") (pin "5") (pinfunction "5_5") (pintype "passive"))
      (node (ref "JP7") (pin "6") (pinfunction "6_6") (pintype "passive"))
      (node (ref "JP8") (pin "4") (pinfunction "4_4") (pintype "passive"))
      (node (ref "Q1") (pin "2") (pinfunction "S_2") (pintype "passive"))
      (node (ref "Q10") (pin "2") (pinfunction "S_2") (pintype "passive"))
      (node (ref "Q11") (pin "2") (pinfunction "S_2") (pintype "passive"))
      (node (ref "Q12") (pin "2") (pinfunction "S_2") (pintype "passive"))
      (node (ref "Q13") (pin "2") (pinfunction "S_2") (pintype "passive"))
      (node (ref "Q14") (pin "2") (pinfunction "S_2") (pintype "passive"))
      (node (ref "Q15") (pin "2") (pinfunction "S_2") (pintype "passive"))
      (node (ref "Q16") (pin "2") (pinfunction "S_2") (pintype "passive"))
      (node (ref "Q2") (pin "2") (pinfunction "S_2") (pintype "passive"))
      (node (ref "Q3") (pin "2") (pinfunction "S_2") (pintype "passive"))
      (node (ref "Q4") (pin "2") (pinfunction "S_2") (pintype "passive"))
      (node (ref "Q5") (pin "2") (pinfunction "S_2") (pintype "passive"))
      (node (ref "Q6") (pin "2") (pinfunction "S_2") (pintype "passive"))
      (node (ref "Q7") (pin "2") (pinfunction "S_2") (pintype "passive"))
      (node (ref "Q8") (pin "2") (pinfunction "S_2") (pintype "passive"))
      (node (ref "Q9") (pin "2") (pinfunction "S_2") (pintype "passive"))
      (node (ref "R2") (pin "1") (pinfunction "1_1") (pintype "passive"))
      (node (ref "R61") (pin "2") (pinfunction "2_2") (pintype "passive"))
      (node (ref "SJ12") (pin "2") (pinfunction "2_2") (pintype "passive"))
      (node (ref "SJ3") (pin "2") (pinfunction "2_2") (pintype "passive"))
      (node (ref "SJ6") (pin "2") (pinfunction "2_2") (pintype "passive"))
      (node (ref "SJ9") (pin "2") (pinfunction "2_2") (pintype "passive"))
      (node (ref "U$1") (pin "GND3") (pinfunction "GND3_GND3") (pintype "power_in"))
      (node (ref "U$1") (pin "GND4") (pinfunction "GND4_GND4") (pintype "power_in"))
      (node (ref "U$1") (pin "GND5") (pinfunction "GND5_GND5") (pintype "power_in"))
      (node (ref "U$1") (pin "GND6") (pinfunction "GND6_GND6") (pintype "power_in"))
      (node (ref "U$1") (pin "GND7") (pinfunction "GND7_GND7") (pintype "power_in"))
      (node (ref "U$1") (pin "GND8") (pinfunction "GND8_GND8") (pintype "power_in"))
      (node (ref "U$2") (pin "3") (pinfunction "VSS_3") (pintype "power_in"))
      (node (ref "U$3") (pin "3") (pinfunction "VSS_3") (pintype "power_in"))
      (node (ref "U$4") (pin "3") (pinfunction "VSS_3") (pintype "power_in"))
      (node (ref "U$5") (pin "3") (pinfunction "VSS_3") (pintype "power_in"))
      (node (ref "U$6") (pin "2") (pinfunction "VSS_2") (pintype "power_in"))
    )
    (net (code "26") (name "I2CSCL") (class "Default")
      (node (ref "JP8") (pin "2") (pinfunction "2_2") (pintype "passive"))
      (node (ref "R63") (pin "2") (pinfunction "2_2") (pintype "passive"))
      (node (ref "U$1") (pin "PB6") (pinfunction "PB6_PB6") (pintype "bidirectional"))
    )
    (net (code "27") (name "I2CSDA") (class "Default")
      (node (ref "JP8") (pin "1") (pinfunction "1_1") (pintype "passive"))
      (node (ref "R62") (pin "2") (pinfunction "2_2") (pintype "passive"))
      (node (ref "U$1") (pin "PB7") (pinfunction "PB7_PB7") (pintype "bidirectional"))
    )
    (net (code "28") (name "ILAT") (class "Default")
      (node (ref "IC1") (pin "15") (pinfunction "SH/~{LD}_15") (pintype "input"))
      (node (ref "IC4") (pin "15") (pinfunction "SH/~{LD}_15") (pintype "input"))
      (node (ref "U$1") (pin "PA6") (pinfunction "PA6_PA6") (pintype "bidirectional"))
    )
    (net (code "29") (name "MISO") (class "Default")
      (node (ref "JP9") (pin "1") (pinfunction "1_1") (pintype "passive"))
      (node (ref "U$1") (pin "PB4") (pinfunction "PB4_PB4") (pintype "bidirectional"))
    )
    (net (code "30") (name "MISO2") (class "Default")
      (node (ref "IC4") (pin "13") (pinfunction "QH_13") (pintype "output"))
      (node (ref "SJ13") (pin "P$2") (pinfunction "2_P$2") (pintype "passive"))
      (node (ref "U$1") (pin "PC2") (pinfunction "PC2_PC2") (pintype "bidirectional"))
    )
    (net (code "31") (name "MOSI") (class "Default")
      (node (ref "IC5") (pin "14") (pinfunction "SER_14") (pintype "input"))
      (node (ref "R20") (pin "1") (pinfunction "1_1") (pintype "passive"))
      (node (ref "SJ15") (pin "1") (pinfunction "1_1") (pintype "passive"))
      (node (ref "SJ17") (pin "P$2") (pinfunction "2_P$2") (pintype "passive"))
      (node (ref "U$1") (pin "PB5") (pinfunction "PB5_PB5") (pintype "bidirectional"))
    )
    (net (code "32") (name "Net-(AP1509-VOUT)") (class "Default")
      (node (ref "AP1509") (pin "2") (pinfunction "VOUT_2") (pintype "bidirectional"))
      (node (ref "D1") (pin "C") (pinfunction "C_C") (pintype "passive"))
      (node (ref "IC10") (pin "7") (pinfunction "OUT_7") (pintype "passive"))
      (node (ref "L1") (pin "2") (pinfunction "2_2") (pintype "passive"))
    )
    (net (code "33") (name "Net-(D2-PadA)") (class "Default")
      (node (ref "D2") (pin "A") (pinfunction "A_A") (pintype "passive"))
      (node (ref "JP4") (pin "4") (pinfunction "4_4") (pintype "passive"))
    )
    (net (code "34") (name "Net-(D2-PadC)") (class "Default")
      (node (ref "D2") (pin "C") (pinfunction "C_C") (pintype "passive"))
      (node (ref "JP4") (pin "1") (pinfunction "1_1") (pintype "passive"))
    )
    (net (code "35") (name "Net-(IC1A-A)") (class "Default")
      (node (ref "IC1") (pin "2") (pinfunction "A_2") (pintype "input"))
      (node (ref "R36") (pin "1") (pinfunction "1_1") (pintype "passive"))
      (node (ref "RN4") (pin "9") (pinfunction "2_9") (pintype "passive"))
    )
    (net (code "36") (name "Net-(IC1A-B)") (class "Default")
      (node (ref "IC1") (pin "3") (pinfunction "B_3") (pintype "input"))
      (node (ref "R37") (pin "1") (pinfunction "1_1") (pintype "passive"))
      (node (ref "RN4") (pin "10") (pinfunction "2_10") (pintype "passive"))
    )
    (net (code "37") (name "Net-(IC1A-C)") (class "Default")
      (node (ref "IC1") (pin "4") (pinfunction "C_4") (pintype "input"))
      (node (ref "R38") (pin "1") (pinfunction "1_1") (pintype "passive"))
      (node (ref "RN4") (pin "11") (pinfunction "2_11") (pintype "passive"))
    )
    (net (code "38") (name "Net-(IC1A-D)") (class "Default")
      (node (ref "IC1") (pin "5") (pinfunction "D_5") (pintype "input"))
      (node (ref "R39") (pin "1") (pinfunction "1_1") (pintype "passive"))
      (node (ref "RN4") (pin "12") (pinfunction "2_12") (pintype "passive"))
    )
    (net (code "39") (name "Net-(IC1A-E)") (class "Default")
      (node (ref "IC1") (pin "10") (pinfunction "E_10") (pintype "input"))
      (node (ref "R41") (pin "1") (pinfunction "1_1") (pintype "passive"))
      (node (ref "RN4") (pin "13") (pinfunction "2_13") (pintype "passive"))
    )
    (net (code "40") (name "Net-(IC1A-F)") (class "Default")
      (node (ref "IC1") (pin "11") (pinfunction "F_11") (pintype "input"))
      (node (ref "R42") (pin "1") (pinfunction "1_1") (pintype "passive"))
      (node (ref "RN4") (pin "14") (pinfunction "2_14") (pintype "passive"))
    )
    (net (code "41") (name "Net-(IC1A-G)") (class "Default")
      (node (ref "IC1") (pin "12") (pinfunction "G_12") (pintype "input"))
      (node (ref "R43") (pin "1") (pinfunction "1_1") (pintype "passive"))
      (node (ref "RN4") (pin "15") (pinfunction "2_15") (pintype "passive"))
    )
    (net (code "42") (name "Net-(IC1A-H)") (class "Default")
      (node (ref "IC1") (pin "14") (pinfunction "H_14") (pintype "input"))
      (node (ref "R44") (pin "1") (pinfunction "1_1") (pintype "passive"))
      (node (ref "RN4") (pin "16") (pinfunction "2_16") (pintype "passive"))
    )
    (net (code "43") (name "Net-(IC2-CD+)") (class "Default")
      (node (ref "IC2") (pin "10") (pinfunction "CD+_10") (pintype "passive"))
      (node (ref "SJ4") (pin "1") (pinfunction "1_1") (pintype "passive"))
      (node (ref "SJ5") (pin "1") (pinfunction "1_1") (pintype "passive"))
      (node (ref "SJ6") (pin "1") (pinfunction "1_1") (pintype "passive"))
    )
    (net (code "44") (name "Net-(IC2-GND)") (class "Default")
      (node (ref "IC2") (pin "9") (pinfunction "GND_9") (pintype "power_in"))
      (node (ref "SJ1") (pin "1") (pinfunction "1_1") (pintype "passive"))
      (node (ref "SJ2") (pin "1") (pinfunction "1_1") (pintype "passive"))
      (node (ref "SJ3") (pin "1") (pinfunction "1_1") (pintype "passive"))
    )
    (net (code "45") (name "Net-(IC2-I1)") (class "Default")
      (node (ref "IC2") (pin "1") (pinfunction "I1_1") (pintype "input"))
      (node (ref "IC5") (pin "15") (pinfunction "QA_15") (pintype "tri_state"))
      (node (ref "R3") (pin "1") (pinfunction "1_1") (pintype "passive"))
    )
    (net (code "46") (name "Net-(IC2-I2)") (class "Default")
      (node (ref "IC2") (pin "2") (pinfunction "I2_2") (pintype "input"))
      (node (ref "IC5") (pin "1") (pinfunction "QB_1") (pintype "tri_state"))
      (node (ref "R4") (pin "1") (pinfunction "1_1") (pintype "passive"))
    )
    (net (code "47") (name "Net-(IC2-I3)") (class "Default")
      (node (ref "IC2") (pin "3") (pinfunction "I3_3") (pintype "input"))
      (node (ref "IC5") (pin "2") (pinfunction "QC_2") (pintype "tri_state"))
      (node (ref "R5") (pin "1") (pinfunction "1_1") (pintype "passive"))
    )
    (net (code "48") (name "Net-(IC2-I4)") (class "Default")
      (node (ref "IC2") (pin "4") (pinfunction "I4_4") (pintype "input"))
      (node (ref "IC5") (pin "3") (pinfunction "QD_3") (pintype "tri_state"))
      (node (ref "R6") (pin "1") (pinfunction "1_1") (pintype "passive"))
    )
    (net (code "49") (name "Net-(IC2-I5)") (class "Default")
      (node (ref "IC2") (pin "5") (pinfunction "I5_5") (pintype "input"))
      (node (ref "IC5") (pin "4") (pinfunction "QE_4") (pintype "tri_state"))
      (node (ref "R7") (pin "1") (pinfunction "1_1") (pintype "passive"))
    )
    (net (code "50") (name "Net-(IC2-I6)") (class "Default")
      (node (ref "IC2") (pin "6") (pinfunction "I6_6") (pintype "input"))
      (node (ref "IC5") (pin "5") (pinfunction "QF_5") (pintype "tri_state"))
      (node (ref "R8") (pin "1") (pinfunction "1_1") (pintype "passive"))
    )
    (net (code "51") (name "Net-(IC2-I7)") (class "Default")
      (node (ref "IC2") (pin "7") (pinfunction "I7_7") (pintype "input"))
      (node (ref "IC5") (pin "6") (pinfunction "QG_6") (pintype "tri_state"))
      (node (ref "R9") (pin "1") (pinfunction "1_1") (pintype "passive"))
    )
    (net (code "52") (name "Net-(IC2-I8)") (class "Default")
      (node (ref "IC2") (pin "8") (pinfunction "I8_8") (pintype "input"))
      (node (ref "IC5") (pin "7") (pinfunction "QH_7") (pintype "tri_state"))
      (node (ref "R10") (pin "1") (pinfunction "1_1") (pintype "passive"))
    )
    (net (code "53") (name "Net-(IC2-O1)") (class "Default")
      (node (ref "IC2") (pin "18") (pinfunction "O1_18") (pintype "open_collector"))
      (node (ref "JP1") (pin "1") (pinfunction "1_1") (pintype "passive"))
      (node (ref "Q1") (pin "3") (pinfunction "D_3") (pintype "passive"))
    )
    (net (code "54") (name "Net-(IC2-O2)") (class "Default")
      (node (ref "IC2") (pin "17") (pinfunction "O2_17") (pintype "open_collector"))
      (node (ref "JP1") (pin "2") (pinfunction "2_2") (pintype "passive"))
      (node (ref "Q2") (pin "3") (pinfunction "D_3") (pintype "passive"))
    )
    (net (code "55") (name "Net-(IC2-O3)") (class "Default")
      (node (ref "IC2") (pin "16") (pinfunction "O3_16") (pintype "open_collector"))
      (node (ref "JP1") (pin "3") (pinfunction "3_3") (pintype "passive"))
      (node (ref "Q3") (pin "3") (pinfunction "D_3") (pintype "passive"))
    )
    (net (code "56") (name "Net-(IC2-O4)") (class "Default")
      (node (ref "IC2") (pin "15") (pinfunction "O4_15") (pintype "open_collector"))
      (node (ref "JP1") (pin "4") (pinfunction "4_4") (pintype "passive"))
      (node (ref "Q4") (pin "3") (pinfunction "D_3") (pintype "passive"))
    )
    (net (code "57") (name "Net-(IC2-O5)") (class "Default")
      (node (ref "IC2") (pin "14") (pinfunction "O5_14") (pintype "open_collector"))
      (node (ref "JP1") (pin "5") (pinfunction "5_5") (pintype "passive"))
      (node (ref "Q5") (pin "3") (pinfunction "D_3") (pintype "passive"))
    )
    (net (code "58") (name "Net-(IC2-O6)") (class "Default")
      (node (ref "IC2") (pin "13") (pinfunction "O6_13") (pintype "open_collector"))
      (node (ref "JP1") (pin "6") (pinfunction "6_6") (pintype "passive"))
      (node (ref "Q6") (pin "3") (pinfunction "D_3") (pintype "passive"))
    )
    (net (code "59") (name "Net-(IC2-O7)") (class "Default")
      (node (ref "IC2") (pin "12") (pinfunction "O7_12") (pintype "open_collector"))
      (node (ref "JP1") (pin "7") (pinfunction "7_7") (pintype "passive"))
      (node (ref "Q7") (pin "3") (pinfunction "D_3") (pintype "passive"))
    )
    (net (code "60") (name "Net-(IC2-O8)") (class "Default")
      (node (ref "IC2") (pin "11") (pinfunction "O8_11") (pintype "open_collector"))
      (node (ref "JP1") (pin "8") (pinfunction "8_8") (pintype "passive"))
      (node (ref "Q8") (pin "3") (pinfunction "D_3") (pintype "passive"))
    )
    (net (code "61") (name "Net-(IC3A-QA)") (class "Default")
      (node (ref "IC3") (pin "15") (pinfunction "QA_15") (pintype "tri_state"))
      (node (ref "IC8") (pin "1") (pinfunction "I1_1") (pintype "input"))
      (node (ref "R11") (pin "1") (pinfunction "1_1") (pintype "passive"))
    )
    (net (code "62") (name "Net-(IC3A-QB)") (class "Default")
      (node (ref "IC3") (pin "1") (pinfunction "QB_1") (pintype "tri_state"))
      (node (ref "IC8") (pin "2") (pinfunction "I2_2") (pintype "input"))
      (node (ref "R12") (pin "1") (pinfunction "1_1") (pintype "passive"))
    )
    (net (code "63") (name "Net-(IC3A-QC)") (class "Default")
      (node (ref "IC3") (pin "2") (pinfunction "QC_2") (pintype "tri_state"))
      (node (ref "IC8") (pin "3") (pinfunction "I3_3") (pintype "input"))
      (node (ref "R13") (pin "1") (pinfunction "1_1") (pintype "passive"))
    )
    (net (code "64") (name "Net-(IC3A-QD)") (class "Default")
      (node (ref "IC3") (pin "3") (pinfunction "QD_3") (pintype "tri_state"))
      (node (ref "IC8") (pin "4") (pinfunction "I4_4") (pintype "input"))
      (node (ref "R14") (pin "1") (pinfunction "1_1") (pintype "passive"))
    )
    (net (code "65") (name "Net-(IC3A-QE)") (class "Default")
      (node (ref "IC3") (pin "4") (pinfunction "QE_4") (pintype "tri_state"))
      (node (ref "IC8") (pin "5") (pinfunction "I5_5") (pintype "input"))
      (node (ref "R15") (pin "1") (pinfunction "1_1") (pintype "passive"))
    )
    (net (code "66") (name "Net-(IC3A-QF)") (class "Default")
      (node (ref "IC3") (pin "5") (pinfunction "QF_5") (pintype "tri_state"))
      (node (ref "IC8") (pin "6") (pinfunction "I6_6") (pintype "input"))
      (node (ref "R16") (pin "1") (pinfunction "1_1") (pintype "passive"))
    )
    (net (code "67") (name "Net-(IC3A-QG)") (class "Default")
      (node (ref "IC3") (pin "6") (pinfunction "QG_6") (pintype "tri_state"))
      (node (ref "IC8") (pin "7") (pinfunction "I7_7") (pintype "input"))
      (node (ref "R17") (pin "1") (pinfunction "1_1") (pintype "passive"))
    )
    (net (code "68") (name "Net-(IC3A-QH)") (class "Default")
      (node (ref "IC3") (pin "7") (pinfunction "QH_7") (pintype "tri_state"))
      (node (ref "IC8") (pin "8") (pinfunction "I8_8") (pintype "input"))
      (node (ref "R18") (pin "1") (pinfunction "1_1") (pintype "passive"))
    )
    (net (code "69") (name "Net-(IC4A-A)") (class "Default")
      (node (ref "IC4") (pin "2") (pinfunction "A_2") (pintype "input"))
      (node (ref "R28") (pin "1") (pinfunction "1_1") (pintype "passive"))
      (node (ref "RN1") (pin "9") (pinfunction "2_9") (pintype "passive"))
    )
    (net (code "70") (name "Net-(IC4A-B)") (class "Default")
      (node (ref "IC4") (pin "3") (pinfunction "B_3") (pintype "input"))
      (node (ref "R29") (pin "1") (pinfunction "1_1") (pintype "passive"))
      (node (ref "RN1") (pin "10") (pinfunction "2_10") (pintype "passive"))
    )
    (net (code "71") (name "Net-(IC4A-C)") (class "Default")
      (node (ref "IC4") (pin "4") (pinfunction "C_4") (pintype "input"))
      (node (ref "R30") (pin "1") (pinfunction "1_1") (pintype "passive"))
      (node (ref "RN1") (pin "11") (pinfunction "2_11") (pintype "passive"))
    )
    (net (code "72") (name "Net-(IC4A-D)") (class "Default")
      (node (ref "IC4") (pin "5") (pinfunction "D_5") (pintype "input"))
      (node (ref "R31") (pin "1") (pinfunction "1_1") (pintype "passive"))
      (node (ref "RN1") (pin "12") (pinfunction "2_12") (pintype "passive"))
    )
    (net (code "73") (name "Net-(IC4A-E)") (class "Default")
      (node (ref "IC4") (pin "10") (pinfunction "E_10") (pintype "input"))
      (node (ref "R32") (pin "1") (pinfunction "1_1") (pintype "passive"))
      (node (ref "RN1") (pin "13") (pinfunction "2_13") (pintype "passive"))
    )
    (net (code "74") (name "Net-(IC4A-F)") (class "Default")
      (node (ref "IC4") (pin "11") (pinfunction "F_11") (pintype "input"))
      (node (ref "R33") (pin "1") (pinfunction "1_1") (pintype "passive"))
      (node (ref "RN1") (pin "14") (pinfunction "2_14") (pintype "passive"))
    )
    (net (code "75") (name "Net-(IC4A-G)") (class "Default")
      (node (ref "IC4") (pin "12") (pinfunction "G_12") (pintype "input"))
      (node (ref "R34") (pin "1") (pinfunction "1_1") (pintype "passive"))
      (node (ref "RN1") (pin "15") (pinfunction "2_15") (pintype "passive"))
    )
    (net (code "76") (name "Net-(IC4A-H)") (class "Default")
      (node (ref "IC4") (pin "14") (pinfunction "H_14") (pintype "input"))
      (node (ref "R35") (pin "1") (pinfunction "1_1") (pintype "passive"))
      (node (ref "RN1") (pin "16") (pinfunction "2_16") (pintype "passive"))
    )
    (net (code "77") (name "Net-(IC6A--IN)") (class "Default")
      (node (ref "IC6") (pin "13") (pinfunction "-IN_13") (pintype "input"))
      (node (ref "IC6") (pin "2") (pinfunction "-IN_2") (pintype "input"))
      (node (ref "IC6") (pin "6") (pinfunction "-IN_6") (pintype "input"))
      (node (ref "IC6") (pin "9") (pinfunction "-IN_9") (pintype "input"))
      (node (ref "IC9") (pin "13") (pinfunction "-IN_13") (pintype "input"))
      (node (ref "IC9") (pin "2") (pinfunction "-IN_2") (pintype "input"))
      (node (ref "IC9") (pin "6") (pinfunction "-IN_6") (pintype "input"))
      (node (ref "IC9") (pin "9") (pinfunction "-IN_9") (pintype "input"))
      (node (ref "R1") (pin "1") (pinfunction "1_1") (pintype "passive"))
      (node (ref "R2") (pin "2") (pinfunction "2_2") (pintype "passive"))
    )
    (net (code "78") (name "Net-(IC6A-OUT)") (class "Default")
      (node (ref "IC6") (pin "1") (pinfunction "OUT_1") (pintype "output"))
      (node (ref "JP15") (pin "3") (pinfunction "3_3") (pintype "passive"))
      (node (ref "JP5") (pin "3") (pinfunction "3_3") (pintype "passive"))
      (node (ref "U$5") (pin "5") (pinfunction "O_5") (pintype "output"))
    )
    (net (code "79") (name "Net-(IC6B-OUT)") (class "Default")
      (node (ref "IC6") (pin "7") (pinfunction "OUT_7") (pintype "output"))
      (node (ref "JP15") (pin "1") (pinfunction "1_1") (pintype "passive"))
      (node (ref "JP5") (pin "1") (pinfunction "1_1") (pintype "passive"))
      (node (ref "U$4") (pin "7") (pinfunction "O_7") (pintype "output"))
    )
    (net (code "80") (name "Net-(IC6C-OUT)") (class "Default")
      (node (ref "IC6") (pin "8") (pinfunction "OUT_8") (pintype "output"))
      (node (ref "JP15") (pin "2") (pinfunction "2_2") (pintype "passive"))
      (node (ref "JP5") (pin "2") (pinfunction "2_2") (pintype "passive"))
      (node (ref "U$4") (pin "5") (pinfunction "O_5") (pintype "output"))
    )
    (net (code "81") (name "Net-(IC6D-OUT)") (class "Default")
      (node (ref "IC6") (pin "14") (pinfunction "OUT_14") (pintype "output"))
      (node (ref "JP15") (pin "4") (pinfunction "4_4") (pintype "passive"))
      (node (ref "JP5") (pin "4") (pinfunction "4_4") (pintype "passive"))
      (node (ref "U$5") (pin "7") (pinfunction "O_7") (pintype "output"))
    )
    (net (code "82") (name "Net-(IC7-RS)") (class "Default")
      (node (ref "IC7") (pin "8") (pinfunction "RS_8") (pintype "input"))
      (node (ref "R61") (pin "1") (pinfunction "1_1") (pintype "passive"))
      (node (ref "U$6") (pin "8") (pinfunction "RS_8") (pintype "bidirectional"))
    )
    (net (code "83") (name "Net-(IC7-VREF)") (class "Default")
      (node (ref "IC7") (pin "5") (pinfunction "VREF_5") (pintype "output"))
      (node (ref "SJ18") (pin "P$2") (pinfunction "2_P$2") (pintype "passive"))
      (node (ref "U$6") (pin "5") (pinfunction "VREF_5") (pintype "bidirectional"))
    )
    (net (code "84") (name "Net-(IC8-CD+)") (class "Default")
      (node (ref "IC8") (pin "10") (pinfunction "CD+_10") (pintype "passive"))
      (node (ref "SJ10") (pin "1") (pinfunction "1_1") (pintype "passive"))
      (node (ref "SJ11") (pin "1") (pinfunction "1_1") (pintype "passive"))
      (node (ref "SJ12") (pin "1") (pinfunction "1_1") (pintype "passive"))
    )
    (net (code "85") (name "Net-(IC8-GND)") (class "Default")
      (node (ref "IC8") (pin "9") (pinfunction "GND_9") (pintype "power_in"))
      (node (ref "SJ7") (pin "1") (pinfunction "1_1") (pintype "passive"))
      (node (ref "SJ8") (pin "1") (pinfunction "1_1") (pintype "passive"))
      (node (ref "SJ9") (pin "1") (pinfunction "1_1") (pintype "passive"))
    )
    (net (code "86") (name "Net-(IC8-O1)") (class "Default")
      (node (ref "IC8") (pin "18") (pinfunction "O1_18") (pintype "open_collector"))
      (node (ref "JP6") (pin "1") (pinfunction "1_1") (pintype "passive"))
      (node (ref "Q9") (pin "3") (pinfunction "D_3") (pintype "passive"))
    )
    (net (code "87") (name "Net-(IC8-O2)") (class "Default")
      (node (ref "IC8") (pin "17") (pinfunction "O2_17") (pintype "open_collector"))
      (node (ref "JP6") (pin "2") (pinfunction "2_2") (pintype "passive"))
      (node (ref "Q10") (pin "3") (pinfunction "D_3") (pintype "passive"))
    )
    (net (code "88") (name "Net-(IC8-O3)") (class "Default")
      (node (ref "IC8") (pin "16") (pinfunction "O3_16") (pintype "open_collector"))
      (node (ref "JP6") (pin "3") (pinfunction "3_3") (pintype "passive"))
      (node (ref "Q11") (pin "3") (pinfunction "D_3") (pintype "passive"))
    )
    (net (code "89") (name "Net-(IC8-O4)") (class "Default")
      (node (ref "IC8") (pin "15") (pinfunction "O4_15") (pintype "open_collector"))
      (node (ref "JP6") (pin "4") (pinfunction "4_4") (pintype "passive"))
      (node (ref "Q12") (pin "3") (pinfunction "D_3") (pintype "passive"))
    )
    (net (code "90") (name "Net-(IC8-O5)") (class "Default")
      (node (ref "IC8") (pin "14") (pinfunction "O5_14") (pintype "open_collector"))
      (node (ref "JP6") (pin "5") (pinfunction "5_5") (pintype "passive"))
      (node (ref "Q13") (pin "3") (pinfunction "D_3") (pintype "passive"))
    )
    (net (code "91") (name "Net-(IC8-O6)") (class "Default")
      (node (ref "IC8") (pin "13") (pinfunction "O6_13") (pintype "open_collector"))
      (node (ref "JP6") (pin "6") (pinfunction "6_6") (pintype "passive"))
      (node (ref "Q14") (pin "3") (pinfunction "D_3") (pintype "passive"))
    )
    (net (code "92") (name "Net-(IC8-O7)") (class "Default")
      (node (ref "IC8") (pin "12") (pinfunction "O7_12") (pintype "open_collector"))
      (node (ref "JP6") (pin "7") (pinfunction "7_7") (pintype "passive"))
      (node (ref "Q15") (pin "3") (pinfunction "D_3") (pintype "passive"))
    )
    (net (code "93") (name "Net-(IC8-O8)") (class "Default")
      (node (ref "IC8") (pin "11") (pinfunction "O8_11") (pintype "open_collector"))
      (node (ref "JP6") (pin "8") (pinfunction "8_8") (pintype "passive"))
      (node (ref "Q16") (pin "3") (pinfunction "D_3") (pintype "passive"))
    )
    (net (code "94") (name "Net-(IC9A-OUT)") (class "Default")
      (node (ref "IC9") (pin "1") (pinfunction "OUT_1") (pintype "output"))
      (node (ref "JP15") (pin "9") (pinfunction "9_9") (pintype "passive"))
      (node (ref "JP5") (pin "7") (pinfunction "7_7") (pintype "passive"))
      (node (ref "U$3") (pin "5") (pinfunction "O_5") (pintype "output"))
    )
    (net (code "95") (name "Net-(IC9B-OUT)") (class "Default")
      (node (ref "IC9") (pin "7") (pinfunction "OUT_7") (pintype "output"))
      (node (ref "JP15") (pin "7") (pinfunction "7_7") (pintype "passive"))
      (node (ref "JP5") (pin "5") (pinfunction "5_5") (pintype "passive"))
      (node (ref "U$2") (pin "7") (pinfunction "O_7") (pintype "output"))
    )
    (net (code "96") (name "Net-(IC9C-OUT)") (class "Default")
      (node (ref "IC9") (pin "8") (pinfunction "OUT_8") (pintype "output"))
      (node (ref "JP15") (pin "8") (pinfunction "8_8") (pintype "passive"))
      (node (ref "JP5") (pin "6") (pinfunction "6_6") (pintype "passive"))
      (node (ref "U$2") (pin "5") (pinfunction "O_5") (pintype "output"))
    )
    (net (code "97") (name "Net-(IC9D-OUT)") (class "Default")
      (node (ref "IC9") (pin "14") (pinfunction "OUT_14") (pintype "output"))
      (node (ref "JP15") (pin "10") (pinfunction "10_10") (pintype "passive"))
      (node (ref "JP5") (pin "8") (pinfunction "8_8") (pintype "passive"))
      (node (ref "U$3") (pin "7") (pinfunction "O_7") (pintype "output"))
    )
    (net (code "98") (name "Net-(J1-Pad4)") (class "Default")
      (node (ref "J1") (pin "4") (pinfunction "4_4") (pintype "passive"))
      (node (ref "J2") (pin "4") (pinfunction "4_4") (pintype "passive"))
    )
    (net (code "99") (name "Net-(J1-Pad5)") (class "Default")
      (node (ref "J1") (pin "5") (pinfunction "5_5") (pintype "passive"))
      (node (ref "J2") (pin "5") (pinfunction "5_5") (pintype "passive"))
    )
    (net (code "100") (name "Net-(J1-Pad8)") (class "Default")
      (node (ref "J1") (pin "8") (pinfunction "8_8") (pintype "passive"))
      (node (ref "J2") (pin "8") (pinfunction "8_8") (pintype "passive"))
      (node (ref "R40") (pin "1") (pinfunction "1_1") (pintype "passive"))
    )
    (net (code "101") (name "Net-(JP4-Pad3)") (class "Default")
      (node (ref "JP4") (pin "3") (pinfunction "3_3") (pintype "passive"))
      (node (ref "R40") (pin "2") (pinfunction "2_2") (pintype "passive"))
    )
    (net (code "102") (name "Net-(JP13-Pad1)") (class "Default")
      (node (ref "JP13") (pin "1") (pinfunction "1_1") (pintype "passive"))
      (node (ref "JP3") (pin "1") (pinfunction "1_1") (pintype "passive"))
      (node (ref "R44") (pin "2") (pinfunction "2_2") (pintype "passive"))
      (node (ref "R53") (pin "2") (pinfunction "2_2") (pintype "passive"))
      (node (ref "RN4") (pin "1") (pinfunction "1_1") (pintype "passive"))
      (node (ref "RN5") (pin "9") (pinfunction "9_9") (pintype "passive"))
    )
    (net (code "103") (name "Net-(JP14-Pad1)") (class "Default")
      (node (ref "JP14") (pin "1") (pinfunction "1_1") (pintype "passive"))
      (node (ref "JP2") (pin "1") (pinfunction "1_1") (pintype "passive"))
      (node (ref "R35") (pin "2") (pinfunction "2_2") (pintype "passive"))
      (node (ref "R45") (pin "2") (pinfunction "2_2") (pintype "passive"))
      (node (ref "RN1") (pin "1") (pinfunction "1_1") (pintype "passive"))
      (node (ref "RN2") (pin "9") (pinfunction "9_9") (pintype "passive"))
    )
    (net (code "104") (name "Net-(Q1-G)") (class "Default")
      (node (ref "Q1") (pin "1") (pinfunction "G_1") (pintype "passive"))
      (node (ref "R3") (pin "2") (pinfunction "2_2") (pintype "passive"))
    )
    (net (code "105") (name "Net-(Q2-G)") (class "Default")
      (node (ref "Q2") (pin "1") (pinfunction "G_1") (pintype "passive"))
      (node (ref "R4") (pin "2") (pinfunction "2_2") (pintype "passive"))
    )
    (net (code "106") (name "Net-(Q3-G)") (class "Default")
      (node (ref "Q3") (pin "1") (pinfunction "G_1") (pintype "passive"))
      (node (ref "R5") (pin "2") (pinfunction "2_2") (pintype "passive"))
    )
    (net (code "107") (name "Net-(Q4-G)") (class "Default")
      (node (ref "Q4") (pin "1") (pinfunction "G_1") (pintype "passive"))
      (node (ref "R6") (pin "2") (pinfunction "2_2") (pintype "passive"))
    )
    (net (code "108") (name "Net-(Q5-G)") (class "Default")
      (node (ref "Q5") (pin "1") (pinfunction "G_1") (pintype "passive"))
      (node (ref "R7") (pin "2") (pinfunction "2_2") (pintype "passive"))
    )
    (net (code "109") (name "Net-(Q6-G)") (class "Default")
      (node (ref "Q6") (pin "1") (pinfunction "G_1") (pintype "passive"))
      (node (ref "R8") (pin "2") (pinfunction "2_2") (pintype "passive"))
    )
    (net (code "110") (name "Net-(Q7-G)") (class "Default")
      (node (ref "Q7") (pin "1") (pinfunction "G_1") (pintype "passive"))
      (node (ref "R9") (pin "2") (pinfunction "2_2") (pintype "passive"))
    )
    (net (code "111") (name "Net-(Q8-G)") (class "Default")
      (node (ref "Q8") (pin "1") (pinfunction "G_1") (pintype "passive"))
      (node (ref "R10") (pin "2") (pinfunction "2_2") (pintype "passive"))
    )
    (net (code "112") (name "Net-(Q9-G)") (class "Default")
      (node (ref "Q9") (pin "1") (pinfunction "G_1") (pintype "passive"))
      (node (ref "R11") (pin "2") (pinfunction "2_2") (pintype "passive"))
    )
    (net (code "113") (name "Net-(Q10-G)") (class "Default")
      (node (ref "Q10") (pin "1") (pinfunction "G_1") (pintype "passive"))
      (node (ref "R12") (pin "2") (pinfunction "2_2") (pintype "passive"))
    )
    (net (code "114") (name "Net-(Q11-G)") (class "Default")
      (node (ref "Q11") (pin "1") (pinfunction "G_1") (pintype "passive"))
      (node (ref "R13") (pin "2") (pinfunction "2_2") (pintype "passive"))
    )
    (net (code "115") (name "Net-(Q12-G)") (class "Default")
      (node (ref "Q12") (pin "1") (pinfunction "G_1") (pintype "passive"))
      (node (ref "R14") (pin "2") (pinfunction "2_2") (pintype "passive"))
    )
    (net (code "116") (name "Net-(Q13-G)") (class "Default")
      (node (ref "Q13") (pin "1") (pinfunction "G_1") (pintype "passive"))
      (node (ref "R15") (pin "2") (pinfunction "2_2") (pintype "passive"))
    )
    (net (code "117") (name "Net-(Q14-G)") (class "Default")
      (node (ref "Q14") (pin "1") (pinfunction "G_1") (pintype "passive"))
      (node (ref "R16") (pin "2") (pinfunction "2_2") (pintype "passive"))
    )
    (net (code "118") (name "Net-(Q15-G)") (class "Default")
      (node (ref "Q15") (pin "1") (pinfunction "G_1") (pintype "passive"))
      (node (ref "R17") (pin "2") (pinfunction "2_2") (pintype "passive"))
    )
    (net (code "119") (name "Net-(Q16-G)") (class "Default")
      (node (ref "Q16") (pin "1") (pinfunction "G_1") (pintype "passive"))
      (node (ref "R18") (pin "2") (pinfunction "2_2") (pintype "passive"))
    )
    (net (code "120") (name "Net-(RN1B-1)") (class "Default")
      (node (ref "JP14") (pin "2") (pinfunction "2_2") (pintype "passive"))
      (node (ref "JP2") (pin "2") (pinfunction "2_2") (pintype "passive"))
      (node (ref "R34") (pin "2") (pinfunction "2_2") (pintype "passive"))
      (node (ref "R46") (pin "1") (pinfunction "1_1") (pintype "passive"))
      (node (ref "RN1") (pin "2") (pinfunction "1_2") (pintype "passive"))
      (node (ref "RN2") (pin "8") (pinfunction "8_8") (pintype "passive"))
    )
    (net (code "121") (name "Net-(RN1C-1)") (class "Default")
      (node (ref "JP14") (pin "3") (pinfunction "3_3") (pintype "passive"))
      (node (ref "JP2") (pin "3") (pinfunction "3_3") (pintype "passive"))
      (node (ref "R33") (pin "2") (pinfunction "2_2") (pintype "passive"))
      (node (ref "R47") (pin "1") (pinfunction "1_1") (pintype "passive"))
      (node (ref "RN1") (pin "3") (pinfunction "1_3") (pintype "passive"))
      (node (ref "RN2") (pin "7") (pinfunction "7_7") (pintype "passive"))
    )
    (net (code "122") (name "Net-(RN1D-1)") (class "Default")
      (node (ref "JP14") (pin "4") (pinfunction "4_4") (pintype "passive"))
      (node (ref "JP2") (pin "4") (pinfunction "4_4") (pintype "passive"))
      (node (ref "R32") (pin "2") (pinfunction "2_2") (pintype "passive"))
      (node (ref "R48") (pin "1") (pinfunction "1_1") (pintype "passive"))
      (node (ref "RN1") (pin "4") (pinfunction "1_4") (pintype "passive"))
      (node (ref "RN2") (pin "6") (pinfunction "6_6") (pintype "passive"))
    )
    (net (code "123") (name "Net-(RN1E-1)") (class "Default")
      (node (ref "JP14") (pin "7") (pinfunction "7_7") (pintype "passive"))
      (node (ref "JP2") (pin "5") (pinfunction "5_5") (pintype "passive"))
      (node (ref "R31") (pin "2") (pinfunction "2_2") (pintype "passive"))
      (node (ref "R49") (pin "1") (pinfunction "1_1") (pintype "passive"))
      (node (ref "RN1") (pin "5") (pinfunction "1_5") (pintype "passive"))
      (node (ref "RN2") (pin "5") (pinfunction "5_5") (pintype "passive"))
    )
    (net (code "124") (name "Net-(RN1F-1)") (class "Default")
      (node (ref "JP14") (pin "8") (pinfunction "8_8") (pintype "passive"))
      (node (ref "JP2") (pin "6") (pinfunction "6_6") (pintype "passive"))
      (node (ref "R30") (pin "2") (pinfunction "2_2") (pintype "passive"))
      (node (ref "R50") (pin "1") (pinfunction "1_1") (pintype "passive"))
      (node (ref "RN1") (pin "6") (pinfunction "1_6") (pintype "passive"))
      (node (ref "RN2") (pin "4") (pinfunction "4_4") (pintype "passive"))
    )
    (net (code "125") (name "Net-(RN1G-1)") (class "Default")
      (node (ref "JP14") (pin "9") (pinfunction "9_9") (pintype "passive"))
      (node (ref "JP2") (pin "7") (pinfunction "7_7") (pintype "passive"))
      (node (ref "R29") (pin "2") (pinfunction "2_2") (pintype "passive"))
      (node (ref "R51") (pin "1") (pinfunction "1_1") (pintype "passive"))
      (node (ref "RN1") (pin "7") (pinfunction "1_7") (pintype "passive"))
      (node (ref "RN2") (pin "3") (pinfunction "3_3") (pintype "passive"))
    )
    (net (code "126") (name "Net-(RN1H-1)") (class "Default")
      (node (ref "JP14") (pin "10") (pinfunction "10_10") (pintype "passive"))
      (node (ref "JP2") (pin "8") (pinfunction "8_8") (pintype "passive"))
      (node (ref "R28") (pin "2") (pinfunction "2_2") (pintype "passive"))
      (node (ref "R52") (pin "1") (pinfunction "1_1") (pintype "passive"))
      (node (ref "RN1") (pin "8") (pinfunction "1_8") (pintype "passive"))
      (node (ref "RN2") (pin "2") (pinfunction "2_2") (pintype "passive"))
    )
    (net (code "127") (name "Net-(RN4B-1)") (class "Default")
      (node (ref "JP13") (pin "2") (pinfunction "2_2") (pintype "passive"))
      (node (ref "JP3") (pin "2") (pinfunction "2_2") (pintype "passive"))
      (node (ref "R43") (pin "2") (pinfunction "2_2") (pintype "passive"))
      (node (ref "R54") (pin "2") (pinfunction "2_2") (pintype "passive"))
      (node (ref "RN4") (pin "2") (pinfunction "1_2") (pintype "passive"))
      (node (ref "RN5") (pin "8") (pinfunction "8_8") (pintype "passive"))
    )
    (net (code "128") (name "Net-(RN4C-1)") (class "Default")
      (node (ref "JP13") (pin "3") (pinfunction "3_3") (pintype "passive"))
      (node (ref "JP3") (pin "3") (pinfunction "3_3") (pintype "passive"))
      (node (ref "R42") (pin "2") (pinfunction "2_2") (pintype "passive"))
      (node (ref "R55") (pin "2") (pinfunction "2_2") (pintype "passive"))
      (node (ref "RN4") (pin "3") (pinfunction "1_3") (pintype "passive"))
      (node (ref "RN5") (pin "7") (pinfunction "7_7") (pintype "passive"))
    )
    (net (code "129") (name "Net-(RN4D-1)") (class "Default")
      (node (ref "JP13") (pin "4") (pinfunction "4_4") (pintype "passive"))
      (node (ref "JP3") (pin "4") (pinfunction "4_4") (pintype "passive"))
      (node (ref "R41") (pin "2") (pinfunction "2_2") (pintype "passive"))
      (node (ref "R56") (pin "2") (pinfunction "2_2") (pintype "passive"))
      (node (ref "RN4") (pin "4") (pinfunction "1_4") (pintype "passive"))
      (node (ref "RN5") (pin "6") (pinfunction "6_6") (pintype "passive"))
    )
    (net (code "130") (name "Net-(RN4E-1)") (class "Default")
      (node (ref "JP13") (pin "7") (pinfunction "7_7") (pintype "passive"))
      (node (ref "JP3") (pin "5") (pinfunction "5_5") (pintype "passive"))
      (node (ref "R39") (pin "2") (pinfunction "2_2") (pintype "passive"))
      (node (ref "R57") (pin "2") (pinfunction "2_2") (pintype "passive"))
      (node (ref "RN4") (pin "5") (pinfunction "1_5") (pintype "passive"))
      (node (ref "RN5") (pin "5") (pinfunction "5_5") (pintype "passive"))
    )
    (net (code "131") (name "Net-(RN4F-1)") (class "Default")
      (node (ref "JP13") (pin "8") (pinfunction "8_8") (pintype "passive"))
      (node (ref "JP3") (pin "6") (pinfunction "6_6") (pintype "passive"))
      (node (ref "R38") (pin "2") (pinfunction "2_2") (pintype "passive"))
      (node (ref "R58") (pin "2") (pinfunction "2_2") (pintype "passive"))
      (node (ref "RN4") (pin "6") (pinfunction "1_6") (pintype "passive"))
      (node (ref "RN5") (pin "4") (pinfunction "4_4") (pintype "passive"))
    )
    (net (code "132") (name "Net-(RN4G-1)") (class "Default")
      (node (ref "JP13") (pin "9") (pinfunction "9_9") (pintype "passive"))
      (node (ref "JP3") (pin "7") (pinfunction "7_7") (pintype "passive"))
      (node (ref "R37") (pin "2") (pinfunction "2_2") (pintype "passive"))
      (node (ref "R59") (pin "2") (pinfunction "2_2") (pintype "passive"))
      (node (ref "RN4") (pin "7") (pinfunction "1_7") (pintype "passive"))
      (node (ref "RN5") (pin "3") (pinfunction "3_3") (pintype "passive"))
    )
    (net (code "133") (name "Net-(RN4H-1)") (class "Default")
      (node (ref "JP13") (pin "10") (pinfunction "10_10") (pintype "passive"))
      (node (ref "JP3") (pin "8") (pinfunction "8_8") (pintype "passive"))
      (node (ref "R36") (pin "2") (pinfunction "2_2") (pintype "passive"))
      (node (ref "R60") (pin "2") (pinfunction "2_2") (pintype "passive"))
      (node (ref "RN4") (pin "8") (pinfunction "1_8") (pintype "passive"))
      (node (ref "RN5") (pin "2") (pinfunction "2_2") (pintype "passive"))
    )
    (net (code "134") (name "Net-(SJ13-1)") (class "Default")
      (node (ref "SJ13") (pin "P$1") (pinfunction "1_P$1") (pintype "passive"))
      (node (ref "U$1") (pin "PB14") (pinfunction "PB14_PB14") (pintype "bidirectional"))
    )
    (net (code "135") (name "Net-(SJ14-1)") (class "Default")
      (node (ref "SJ14") (pin "P$1") (pinfunction "1_P$1") (pintype "passive"))
      (node (ref "U$1") (pin "VIN2") (pinfunction "VIN2_VIN2") (pintype "power_in"))
    )
    (net (code "136") (name "Net-(SJ16-2)") (class "Default")
      (node (ref "JP9") (pin "2") (pinfunction "2_2") (pintype "passive"))
      (node (ref "SJ15") (pin "2") (pinfunction "2_2") (pintype "passive"))
      (node (ref "SJ16") (pin "P$2") (pinfunction "2_P$2") (pintype "passive"))
    )
    (net (code "137") (name "OLAT") (class "Default")
      (node (ref "IC3") (pin "12") (pinfunction "RCK_12") (pintype "input"))
      (node (ref "IC5") (pin "12") (pinfunction "RCK_12") (pintype "input"))
      (node (ref "R21") (pin "1") (pinfunction "1_1") (pintype "passive"))
      (node (ref "U$1") (pin "PA8") (pinfunction "PA8_PA8") (pintype "bidirectional"))
    )
    (net (code "138") (name "SCK") (class "Default")
      (node (ref "IC3") (pin "11") (pinfunction "SCK_11") (pintype "input"))
      (node (ref "IC5") (pin "11") (pinfunction "SCK_11") (pintype "input"))
      (node (ref "JP9") (pin "3") (pinfunction "3_3") (pintype "passive"))
      (node (ref "R19") (pin "1") (pinfunction "1_1") (pintype "passive"))
      (node (ref "U$1") (pin "PB3") (pinfunction "PB3_PB3") (pintype "bidirectional"))
    )
    (net (code "139") (name "SCK2") (class "Default")
      (node (ref "IC1") (pin "7") (pinfunction "CLK_7") (pintype "input"))
      (node (ref "IC4") (pin "7") (pinfunction "CLK_7") (pintype "input"))
      (node (ref "U$1") (pin "PB10") (pinfunction "PB10_PB10") (pintype "bidirectional"))
    )
    (net (code "140") (name "SLNK1") (class "Default")
      (node (ref "IC3") (pin "14") (pinfunction "SER_14") (pintype "input"))
      (node (ref "IC5") (pin "9") (pinfunction "QH*_9") (pintype "tri_state"))
      (node (ref "SJ17") (pin "P$1") (pinfunction "1_P$1") (pintype "passive"))
    )
    (net (code "141") (name "SLNK2") (class "Default")
      (node (ref "IC3") (pin "9") (pinfunction "QH*_9") (pintype "tri_state"))
      (node (ref "SJ16") (pin "P$1") (pinfunction "1_P$1") (pintype "passive"))
    )
    (net (code "142") (name "SLNK3") (class "Default")
      (node (ref "IC1") (pin "13") (pinfunction "QH_13") (pintype "output"))
      (node (ref "IC4") (pin "1") (pinfunction "SER_1") (pintype "input"))
    )
    (net (code "143") (name "SRV1") (class "Default")
      (node (ref "JP7") (pin "2") (pinfunction "2_2") (pintype "passive"))
      (node (ref "R25") (pin "2") (pinfunction "2_2") (pintype "passive"))
      (node (ref "U$1") (pin "PC9") (pinfunction "PC9_PC9") (pintype "bidirectional"))
    )
    (net (code "144") (name "SRV2") (class "Default")
      (node (ref "JP7") (pin "1") (pinfunction "1_1") (pintype "passive"))
      (node (ref "R24") (pin "2") (pinfunction "2_2") (pintype "passive"))
      (node (ref "U$1") (pin "PC7") (pinfunction "PC7_PC7") (pintype "bidirectional"))
    )
    (net (code "145") (name "SRV3") (class "Default")
      (node (ref "JP11") (pin "2") (pinfunction "2_2") (pintype "passive"))
      (node (ref "R26") (pin "2") (pinfunction "2_2") (pintype "passive"))
      (node (ref "U$1") (pin "PC8") (pinfunction "PC8_PC8") (pintype "bidirectional"))
    )
    (net (code "146") (name "SRV4") (class "Default")
      (node (ref "JP11") (pin "1") (pinfunction "1_1") (pintype "passive"))
      (node (ref "R27") (pin "2") (pinfunction "2_2") (pintype "passive"))
      (node (ref "U$1") (pin "PC6") (pinfunction "PC6_PC6") (pintype "bidirectional"))
    )
    (net (code "147") (name "TIN3") (class "Default")
      (node (ref "IC9") (pin "10") (pinfunction "+IN_10") (pintype "input"))
      (node (ref "U$1") (pin "PB15") (pinfunction "PB15_PB15") (pintype "bidirectional"))
      (node (ref "U$2") (pin "4") (pinfunction "I_4") (pintype "input"))
    )
    (net (code "148") (name "TIN4") (class "Default")
      (node (ref "IC9") (pin "12") (pinfunction "+IN_12") (pintype "input"))
      (node (ref "U$1") (pin "PB12") (pinfunction "PB12_PB12") (pintype "bidirectional"))
      (node (ref "U$3") (pin "2") (pinfunction "I_2") (pintype "input"))
    )
    (net (code "149") (name "V+") (class "Default")
      (node (ref "AP1509") (pin "3") (pinfunction "FB_3") (pintype "bidirectional"))
      (node (ref "C1") (pin "1") (pinfunction "1_1") (pintype "passive"))
      (node (ref "C2") (pin "+") (pinfunction "+_+") (pintype "passive"))
      (node (ref "IC10") (pin "1") (pinfunction "FB_1") (pintype "input"))
      (node (ref "L1") (pin "1") (pinfunction "1_1") (pintype "passive"))
      (node (ref "U$1") (pin "E5V") (pinfunction "E5V_E5V") (pintype "power_in"))
    )
    (net (code "150") (name "unconnected-(H1-MOUNT-PadB3,3)") (class "Default")
      (node (ref "H1") (pin "B3,3") (pinfunction "MOUNT_B3,3") (pintype "passive"))
    )
    (net (code "151") (name "unconnected-(H2-MOUNT-PadB3,3)") (class "Default")
      (node (ref "H2") (pin "B3,3") (pinfunction "MOUNT_B3,3") (pintype "passive"))
    )
    (net (code "152") (name "unconnected-(H3-MOUNT-PadB3,3)") (class "Default")
      (node (ref "H3") (pin "B3,3") (pinfunction "MOUNT_B3,3") (pintype "passive"))
    )
    (net (code "153") (name "unconnected-(H4-MOUNT-PadB3,3)") (class "Default")
      (node (ref "H4") (pin "B3,3") (pinfunction "MOUNT_B3,3") (pintype "passive"))
    )
    (net (code "154") (name "unconnected-(J3-Pad2)") (class "Default")
      (node (ref "J3") (pin "2") (pinfunction "2_2") (pintype "passive"))
    )
    (net (code "155") (name "unconnected-(U$1-PadBOOT0)") (class "Default")
      (node (ref "U$1") (pin "BOOT0") (pinfunction "BOOT0_BOOT0") (pintype "bidirectional"))
    )
    (net (code "156") (name "unconnected-(U$1-PadIOREF2)") (class "Default")
      (node (ref "U$1") (pin "IOREF2") (pinfunction "IOREF2_IOREF2") (pintype "input"))
    )
    (net (code "157") (name "unconnected-(U$1-PadNC1-PF7)") (class "Default")
      (node (ref "U$1") (pin "NC1-PF7") (pinfunction "NC1-PF7_NC1-PF7") (pintype "bidirectional"))
    )
    (net (code "158") (name "unconnected-(U$1-PadNC2-PF6)") (class "Default")
      (node (ref "U$1") (pin "NC2-PF6") (pinfunction "NC2-PF6_NC2-PF6") (pintype "bidirectional"))
    )
    (net (code "159") (name "unconnected-(U$1-PadNC3)") (class "Default")
      (node (ref "U$1") (pin "NC3") (pinfunction "NC3_NC3") (pintype "no_connect"))
    )
    (net (code "160") (name "unconnected-(U$1-PadNC4)") (class "Default")
      (node (ref "U$1") (pin "NC4") (pinfunction "NC4_NC4") (pintype "no_connect"))
    )
    (net (code "161") (name "unconnected-(U$1-PadNC5-PD8)") (class "Default")
      (node (ref "U$1") (pin "NC5-PD8") (pinfunction "NC5-PD8_NC5-PD8") (pintype "bidirectional"))
    )
    (net (code "162") (name "unconnected-(U$1-PadNC6-PB11)") (class "Default")
      (node (ref "U$1") (pin "NC6-PB11") (pinfunction "NC6-PB11_NC6-PB11") (pintype "no_connect"))
    )
    (net (code "163") (name "unconnected-(U$1-PadNC7-PF5)") (class "Default")
      (node (ref "U$1") (pin "NC7-PF5") (pinfunction "NC7-PF5_NC7-PF5") (pintype "bidirectional"))
    )
    (net (code "164") (name "unconnected-(U$1-PadNC8-PF4)") (class "Default")
      (node (ref "U$1") (pin "NC8-PF4") (pinfunction "NC8-PF4_NC8-PF4") (pintype "bidirectional"))
    )
    (net (code "165") (name "unconnected-(U$1-PadNRESET)") (class "Default")
      (node (ref "U$1") (pin "NRESET") (pinfunction "NRESET_NRESET") (pintype "input"))
    )
    (net (code "166") (name "unconnected-(U$1-PadPA1)") (class "Default")
      (node (ref "U$1") (pin "PA1") (pinfunction "PA1_PA1") (pintype "bidirectional"))
    )
    (net (code "167") (name "unconnected-(U$1-PadPA2)") (class "Default")
      (node (ref "U$1") (pin "PA2") (pinfunction "PA2_PA2") (pintype "bidirectional"))
    )
    (net (code "168") (name "unconnected-(U$1-PadPA3)") (class "Default")
      (node (ref "U$1") (pin "PA3") (pinfunction "PA3_PA3") (pintype "bidirectional"))
    )
    (net (code "169") (name "unconnected-(U$1-PadPA5)") (class "Default")
      (node (ref "U$1") (pin "PA5") (pinfunction "PA5_PA5") (pintype "bidirectional"))
    )
    (net (code "170") (name "unconnected-(U$1-PadPA7)") (class "Default")
      (node (ref "U$1") (pin "PA7") (pinfunction "PA7_PA7") (pintype "bidirectional"))
    )
    (net (code "171") (name "unconnected-(U$1-PadPA9)") (class "Default")
      (node (ref "U$1") (pin "PA9") (pinfunction "PA9_PA9") (pintype "bidirectional"))
    )
    (net (code "172") (name "unconnected-(U$1-PadPA10)") (class "Default")
      (node (ref "U$1") (pin "PA10") (pinfunction "PA10_PA10") (pintype "bidirectional"))
    )
    (net (code "173") (name "unconnected-(U$1-PadPA11)") (class "Default")
      (node (ref "U$1") (pin "PA11") (pinfunction "PA11_PA11") (pintype "bidirectional"))
    )
    (net (code "174") (name "unconnected-(U$1-PadPA12)") (class "Default")
      (node (ref "U$1") (pin "PA12") (pinfunction "PA12_PA12") (pintype "bidirectional"))
    )
    (net (code "175") (name "unconnected-(U$1-PadPA13)") (class "Default")
      (node (ref "U$1") (pin "PA13") (pinfunction "PA13_PA13") (pintype "bidirectional"))
    )
    (net (code "176") (name "unconnected-(U$1-PadPA14)") (class "Default")
      (node (ref "U$1") (pin "PA14") (pinfunction "PA14_PA14") (pintype "bidirectional"))
    )
    (net (code "177") (name "unconnected-(U$1-PadPB0)") (class "Default")
      (node (ref "U$1") (pin "PB0") (pinfunction "PB0_PB0") (pintype "bidirectional"))
    )
    (net (code "178") (name "unconnected-(U$1-PadPB13)") (class "Default")
      (node (ref "U$1") (pin "PB13") (pinfunction "PB13_PB13") (pintype "bidirectional"))
    )
    (net (code "179") (name "unconnected-(U$1-PadPC1)") (class "Default")
      (node (ref "U$1") (pin "PC1") (pinfunction "PC1_PC1") (pintype "bidirectional"))
    )
    (net (code "180") (name "unconnected-(U$1-PadPC4)") (class "Default")
      (node (ref "U$1") (pin "PC4") (pinfunction "PC4_PC4") (pintype "bidirectional"))
    )
    (net (code "181") (name "unconnected-(U$1-PadPC5)") (class "Default")
      (node (ref "U$1") (pin "PC5") (pinfunction "PC5_PC5") (pintype "bidirectional"))
    )
    (net (code "182") (name "unconnected-(U$1-PadPC13)") (class "Default")
      (node (ref "U$1") (pin "PC13") (pinfunction "PC13_PC13") (pintype "bidirectional"))
    )
    (net (code "183") (name "unconnected-(U$1-PadPC14)") (class "Default")
      (node (ref "U$1") (pin "PC14") (pinfunction "PC14_PC14") (pintype "bidirectional"))
    )
    (net (code "184") (name "unconnected-(U$1-PadPC15)") (class "Default")
      (node (ref "U$1") (pin "PC15") (pinfunction "PC15_PC15") (pintype "bidirectional"))
    )
    (net (code "185") (name "unconnected-(U$1-PadPF0-PH0)") (class "Default")
      (node (ref "U$1") (pin "PF0-PH0") (pinfunction "PF0-PH0_PF0-PH0") (pintype "bidirectional"))
    )
  )
)
